# duckypad_buzz.net
KiCad netlist of a schematic drawn in EAGLE
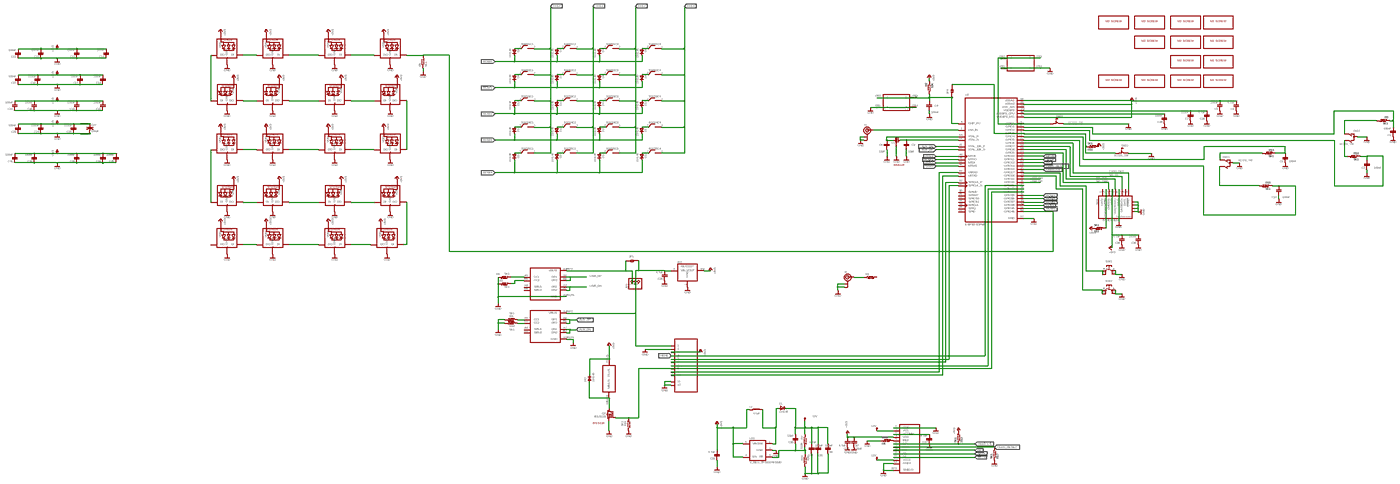
[diagram p0: schematic, sheet 1, overview]
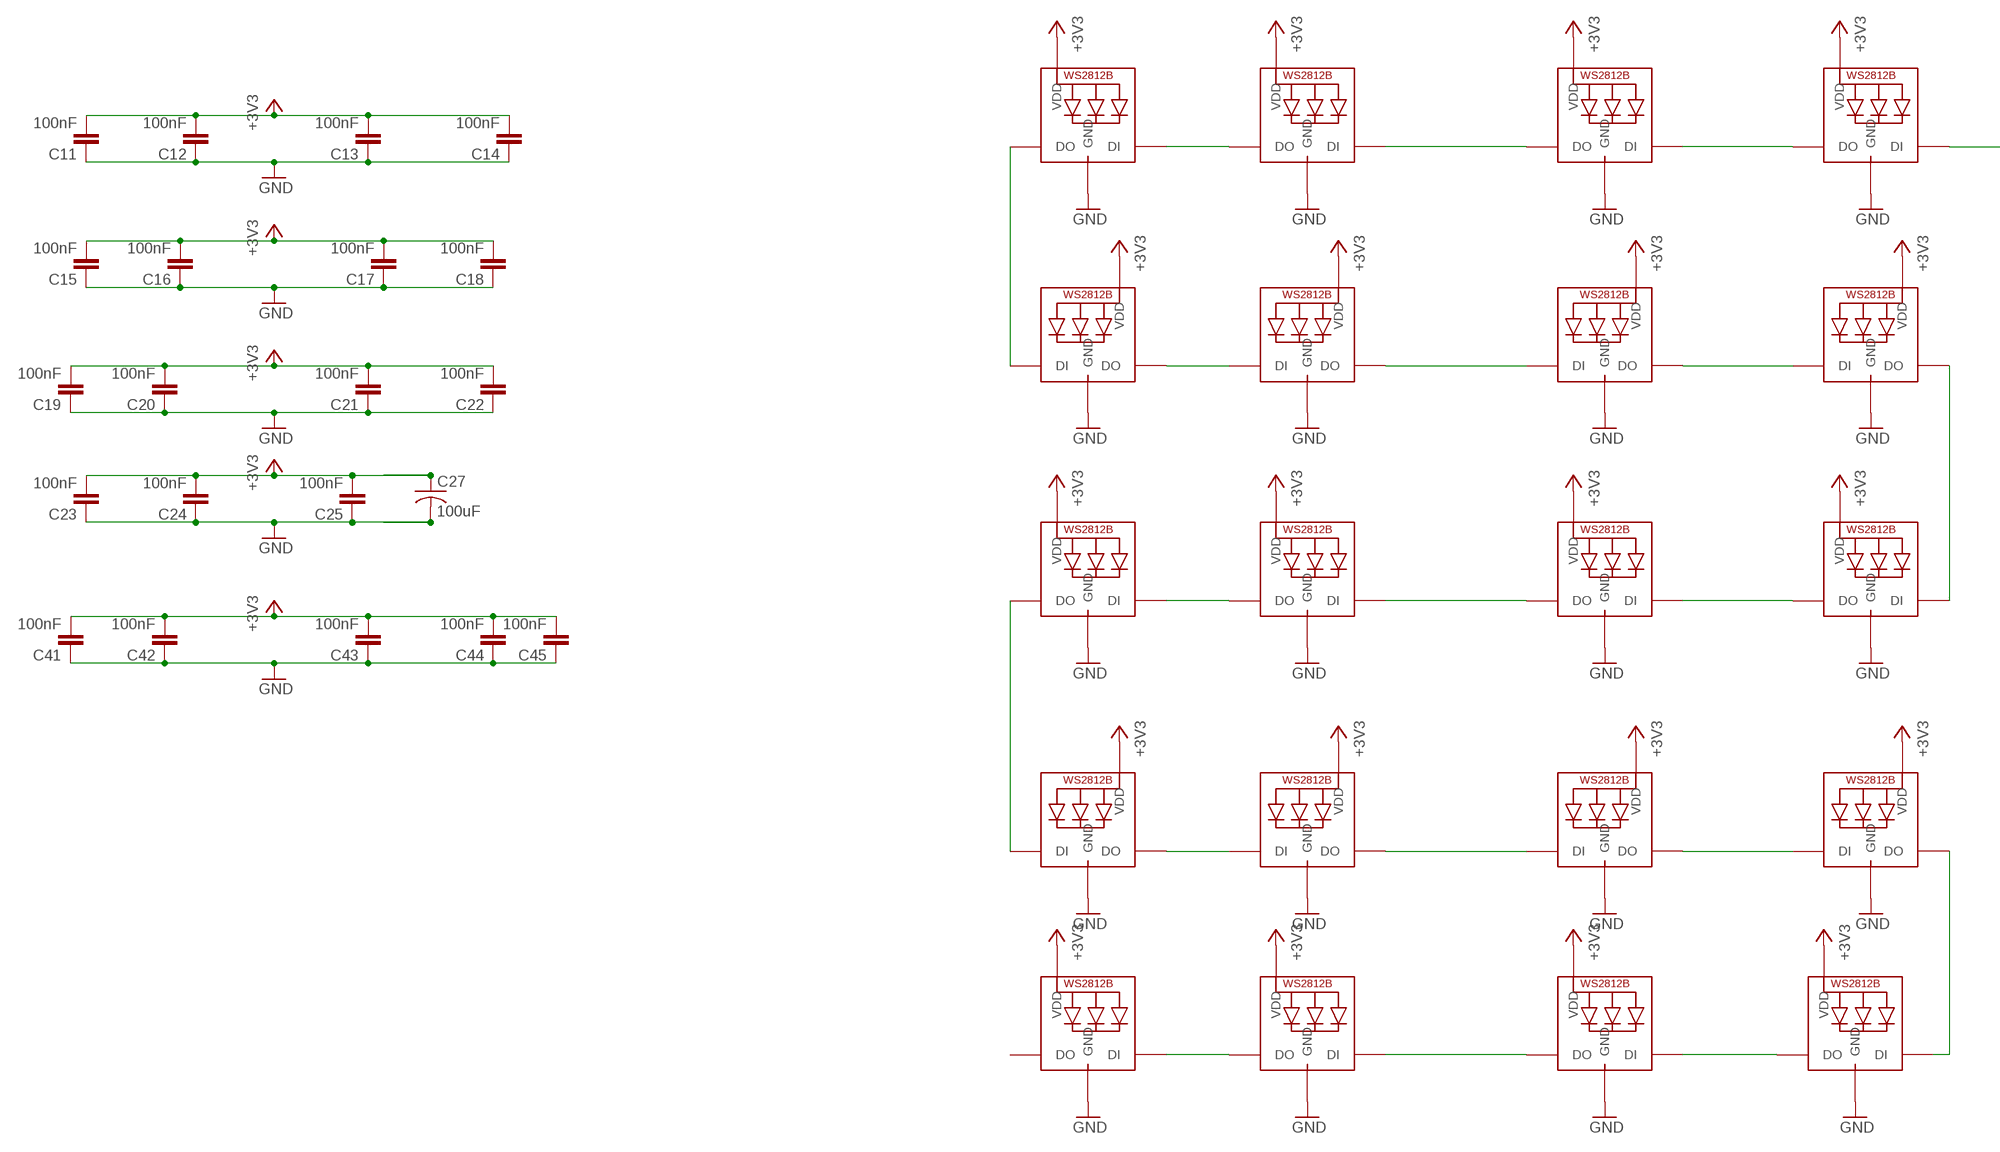
[diagram p1: schematic, sheet 1, part 1 of 4]
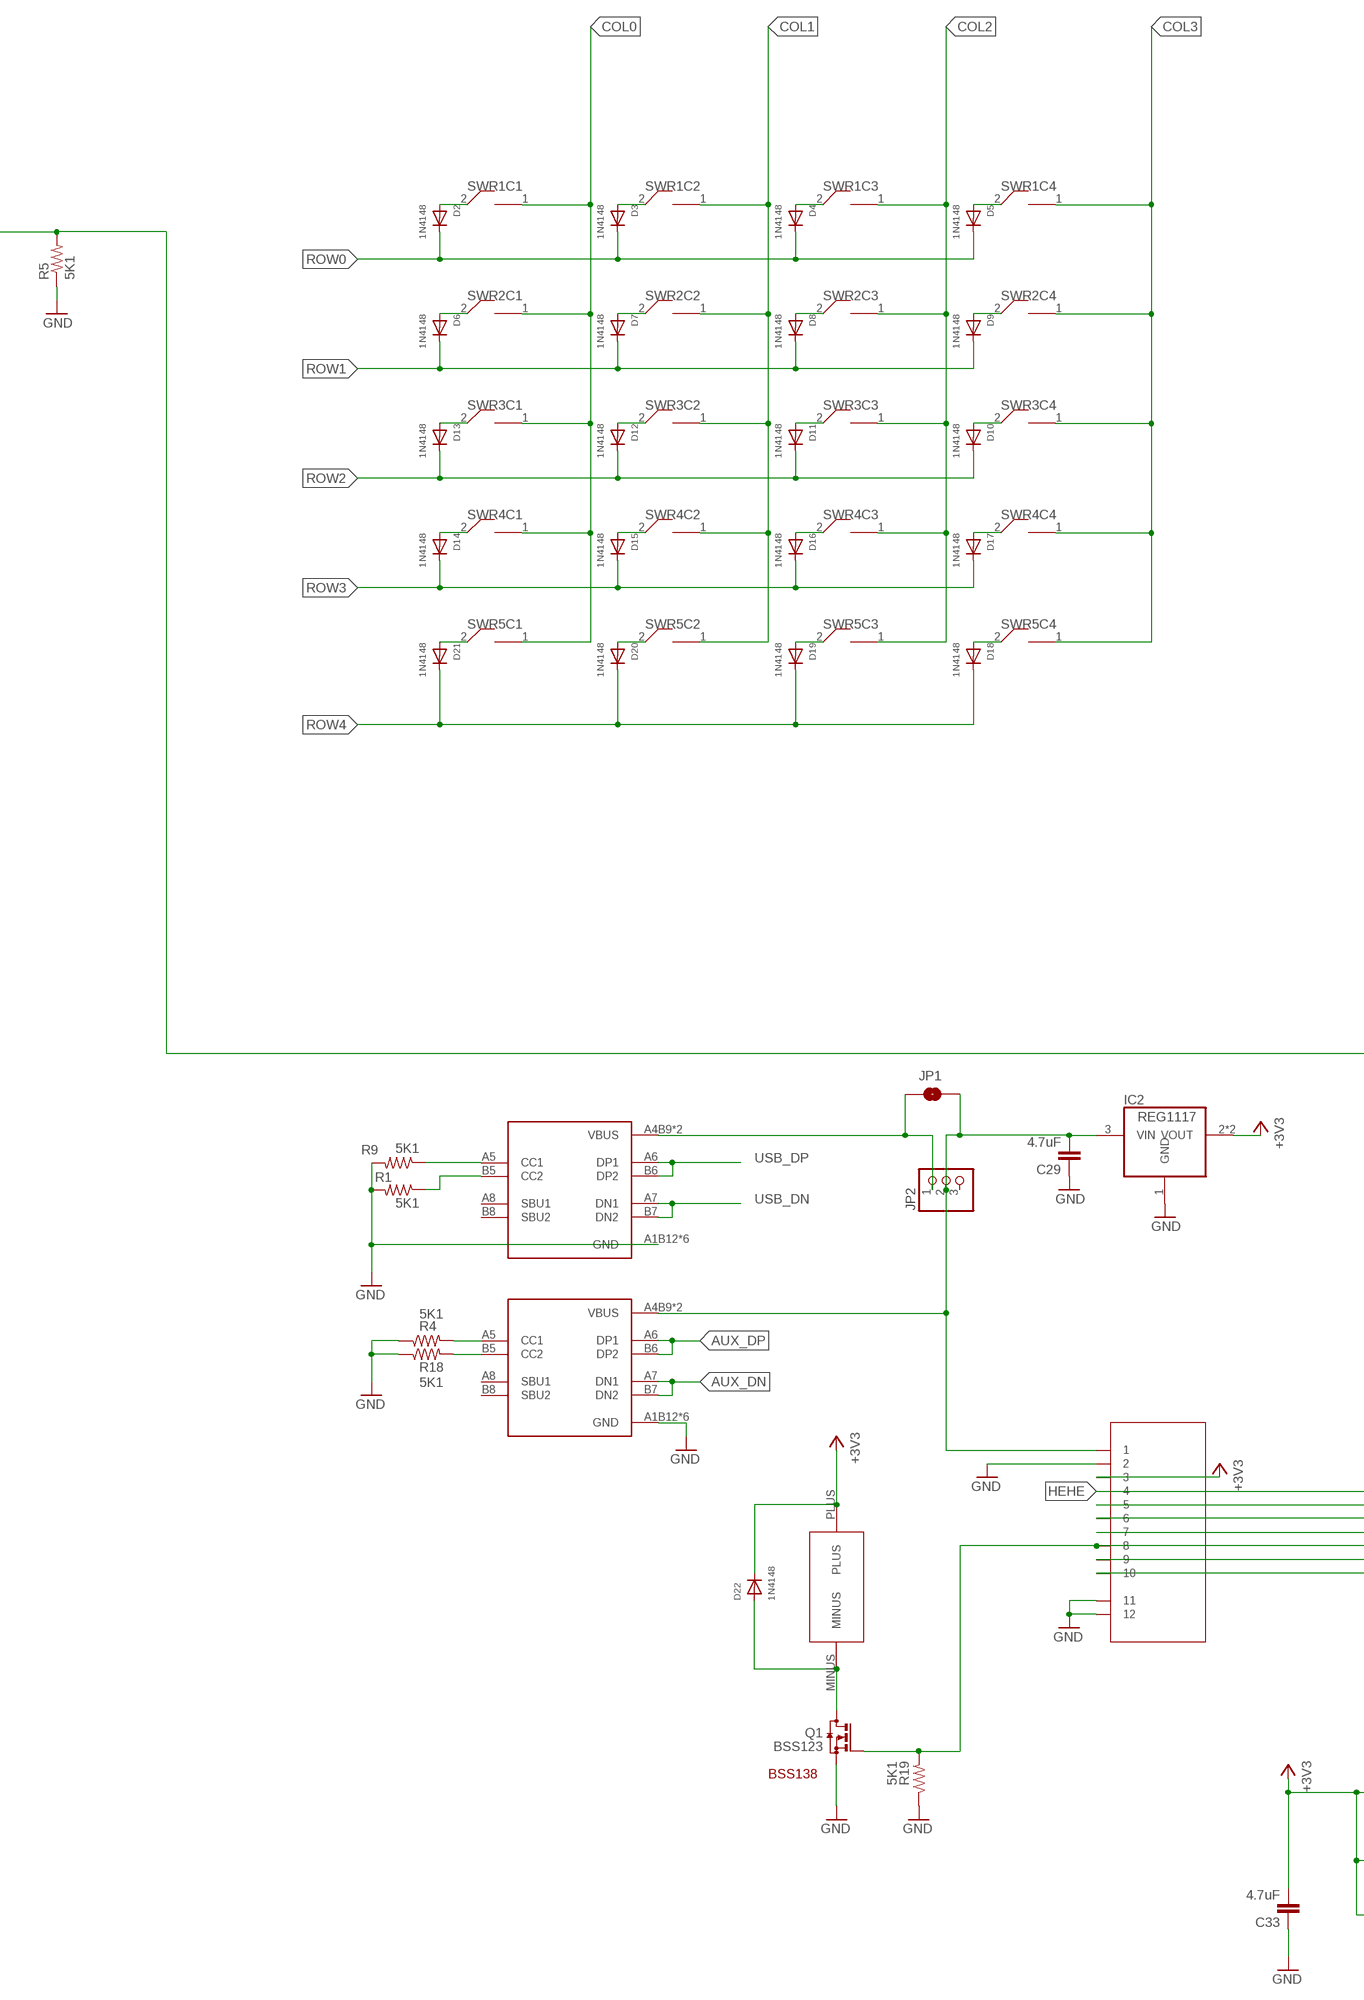
[diagram p2: schematic, sheet 1, part 2 of 4]
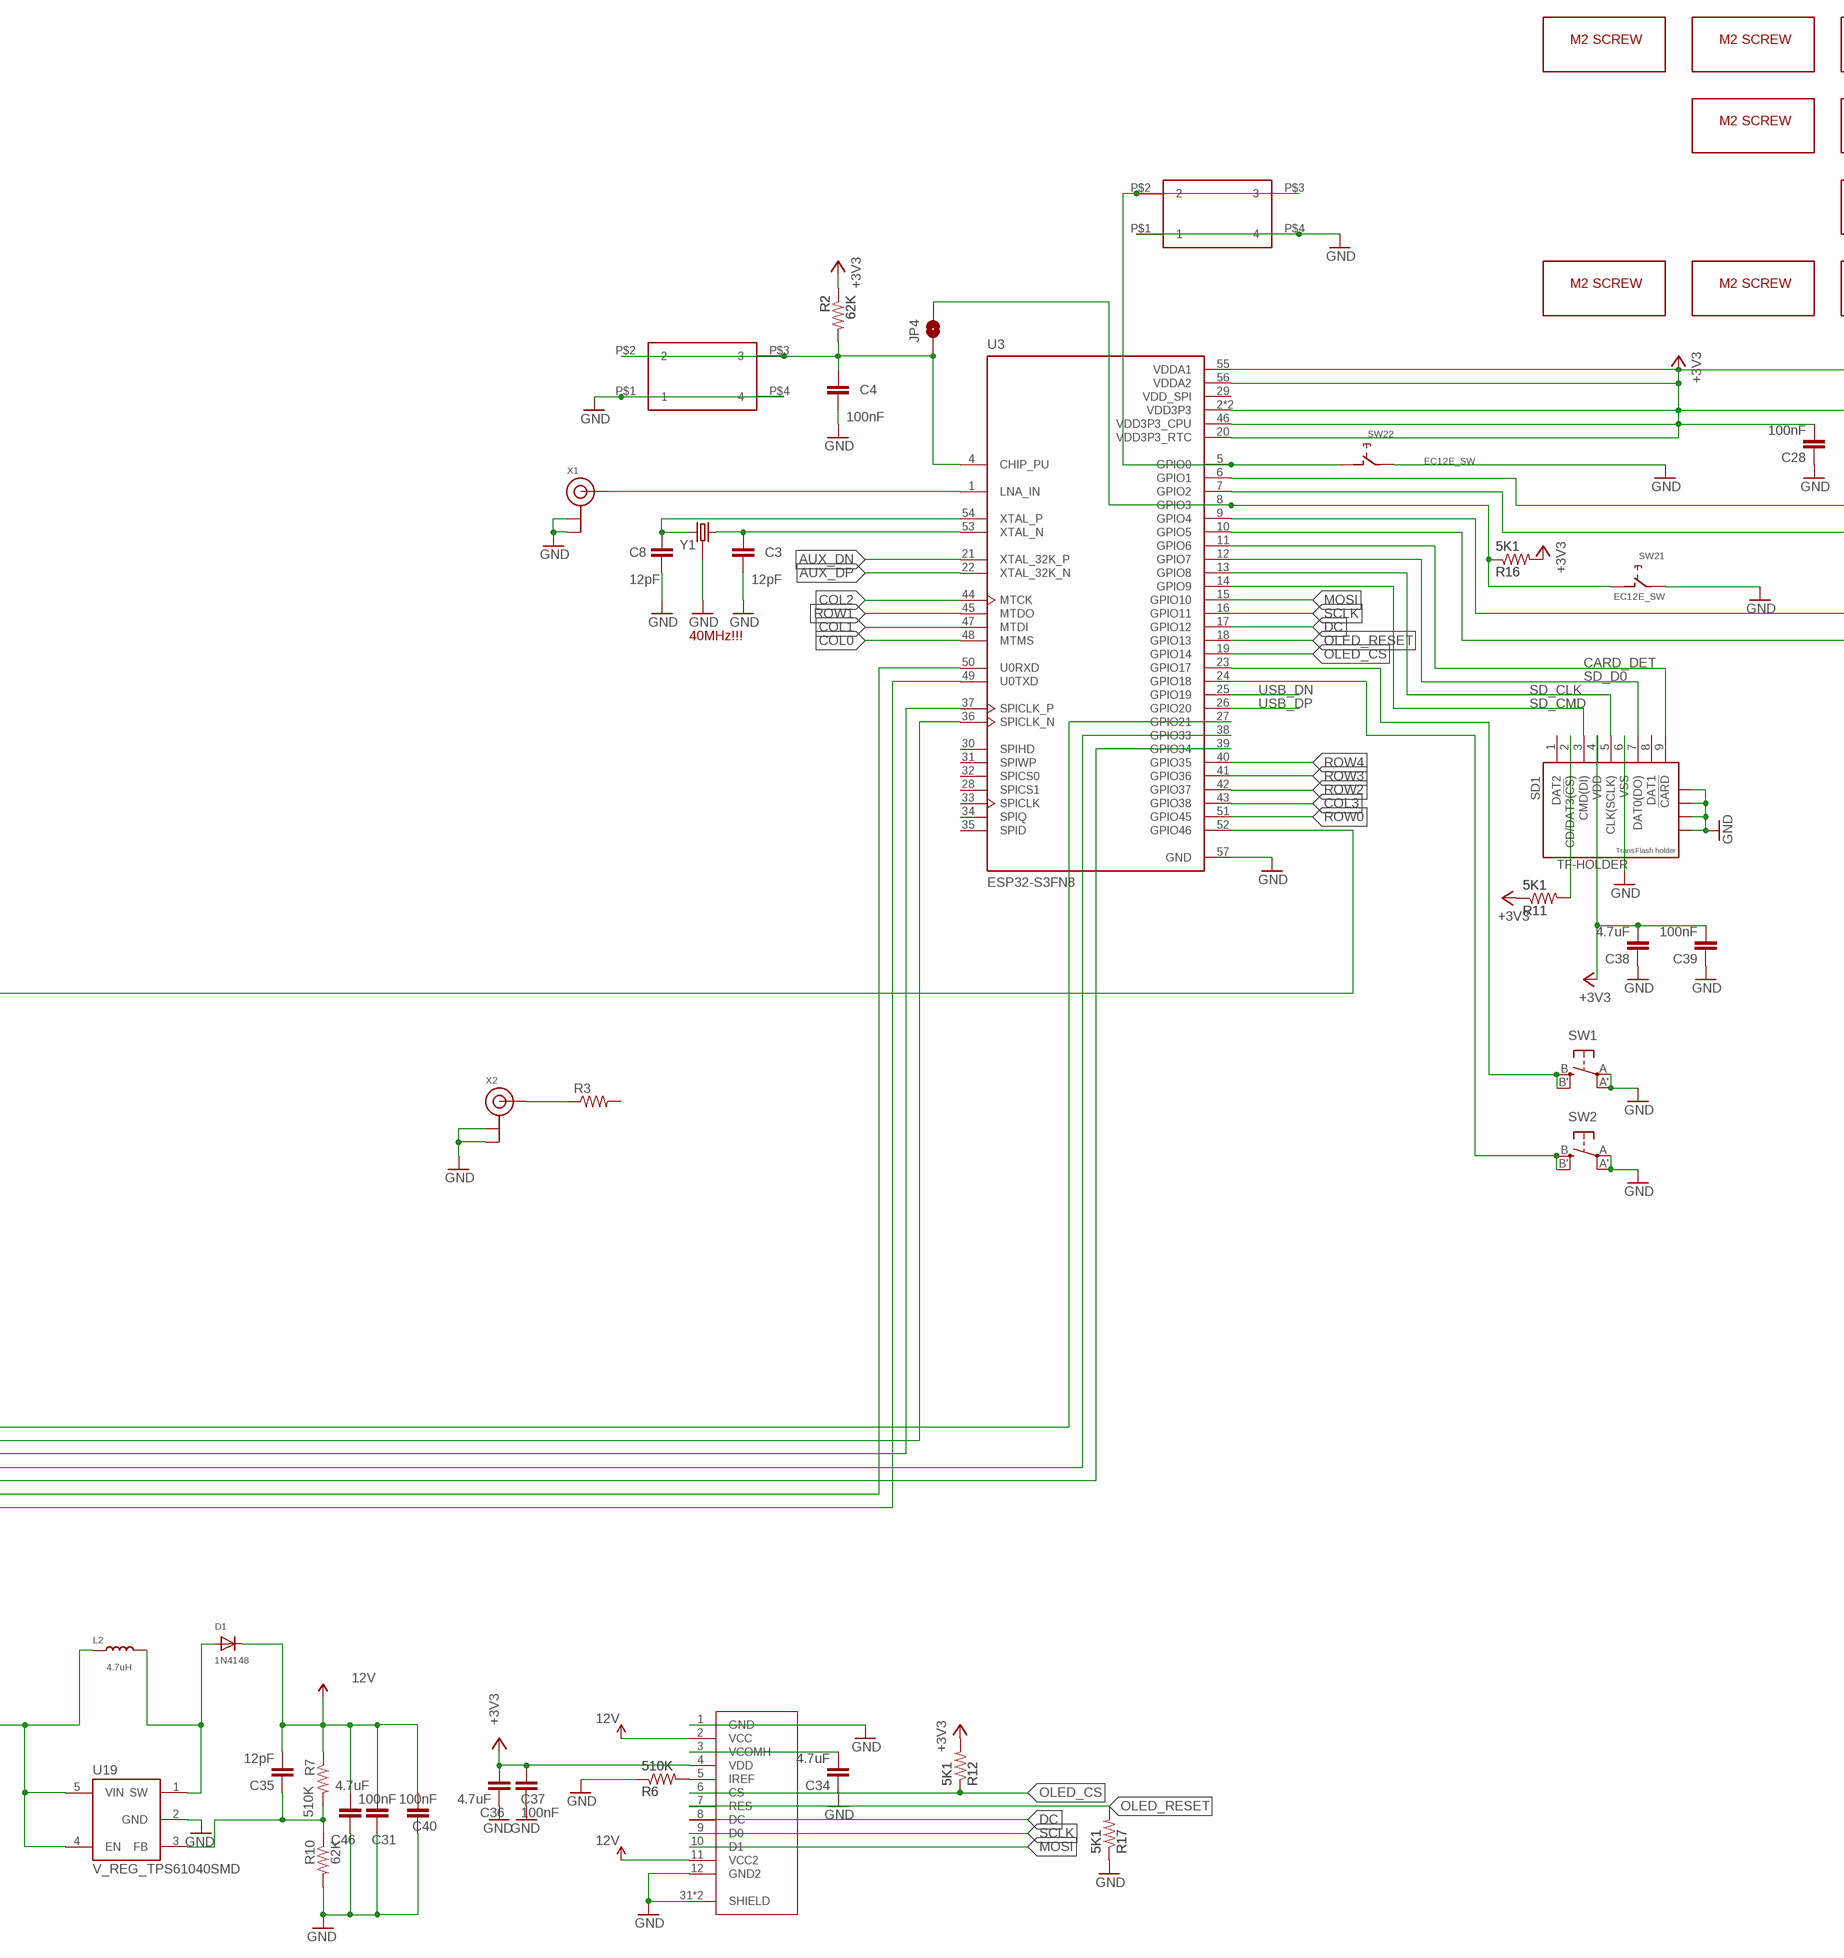
[diagram p3: schematic, sheet 1, part 3 of 4]
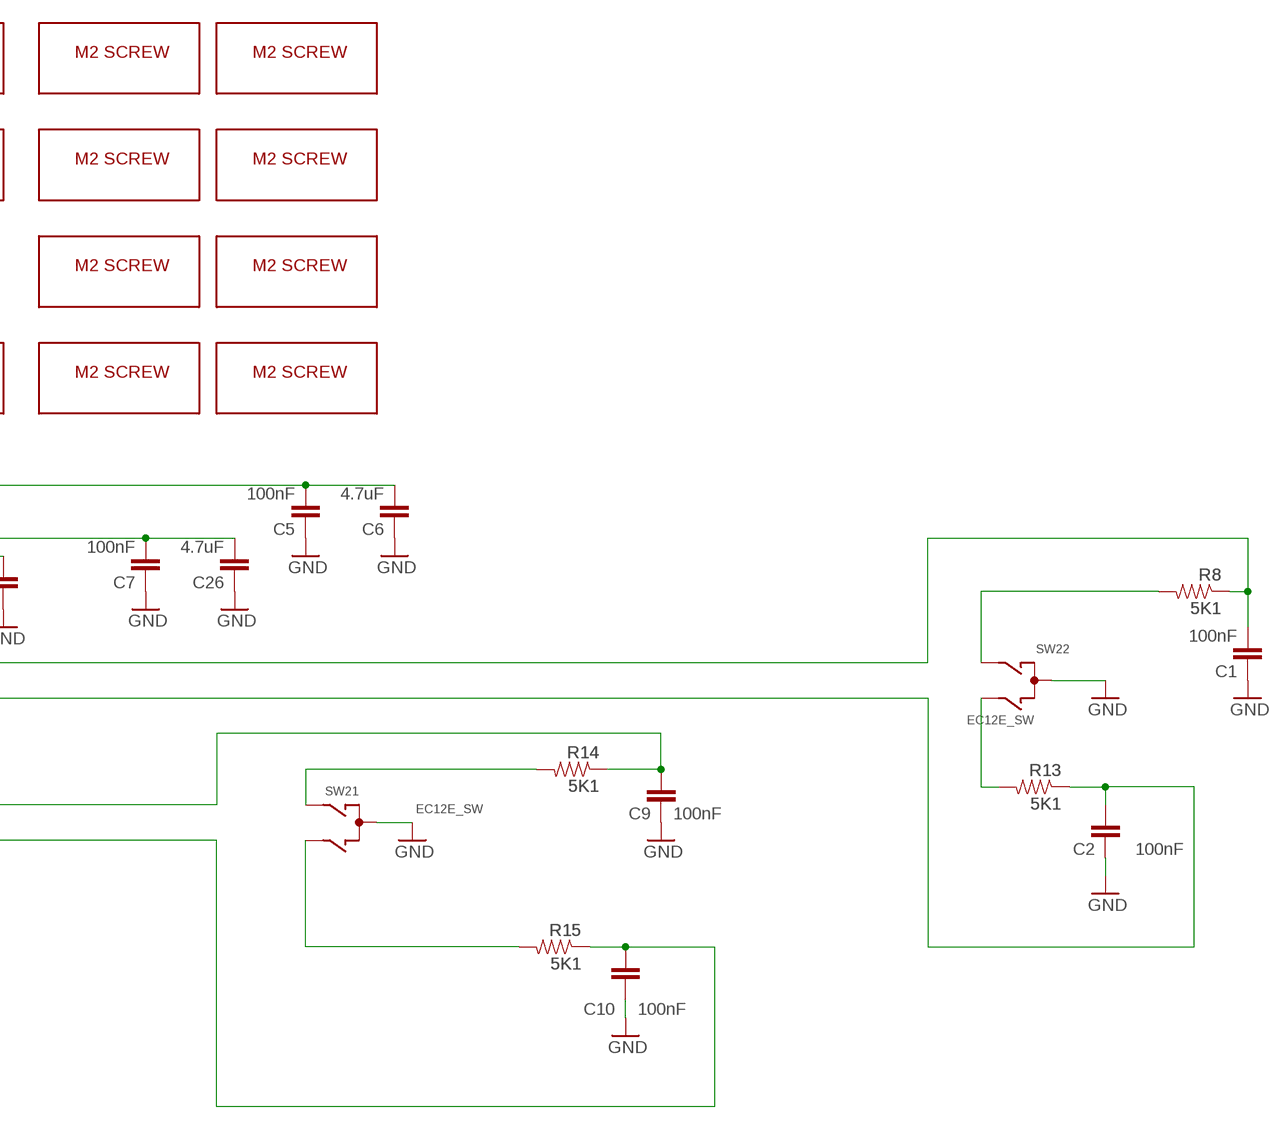
[diagram p4: schematic, sheet 1, part 4 of 4]

(export (version "E")
  (design (tool "Eeschema 10.0.6"))
  (components
    (comp (ref "BZ1")
      (value "BUZZ40402")
      (footprint "eagle-import:BUZZ")
      (libsource (lib "eagle-import") (part "BUZZ40402"))
    )
    (comp (ref "C1")
      (value "100nF")
      (footprint "eagle-import:0805")
      (libsource (lib "eagle-import") (part "CAP0805"))
    )
    (comp (ref "C2")
      (value "100nF")
      (footprint "eagle-import:0805")
      (libsource (lib "eagle-import") (part "CAP0805"))
    )
    (comp (ref "C3")
      (value "12pF")
      (footprint "eagle-import:0805")
      (libsource (lib "eagle-import") (part "CAP0805"))
    )
    (comp (ref "C4")
      (value "100nF")
      (footprint "eagle-import:0805")
      (libsource (lib "eagle-import") (part "CAP0805"))
    )
    (comp (ref "C5")
      (value "100nF")
      (footprint "eagle-import:0805")
      (libsource (lib "eagle-import") (part "CAP0805"))
    )
    (comp (ref "C6")
      (value "4.7uF")
      (footprint "eagle-import:0805")
      (libsource (lib "eagle-import") (part "CAP0805"))
    )
    (comp (ref "C7")
      (value "100nF")
      (footprint "eagle-import:0805")
      (libsource (lib "eagle-import") (part "CAP0805"))
    )
    (comp (ref "C8")
      (value "12pF")
      (footprint "eagle-import:0805")
      (libsource (lib "eagle-import") (part "CAP0805"))
    )
    (comp (ref "C9")
      (value "100nF")
      (footprint "eagle-import:0805")
      (libsource (lib "eagle-import") (part "CAP0805"))
    )
    (comp (ref "C10")
      (value "100nF")
      (footprint "eagle-import:0805")
      (libsource (lib "eagle-import") (part "CAP0805"))
    )
    (comp (ref "C11")
      (value "100nF")
      (footprint "eagle-import:0805")
      (libsource (lib "eagle-import") (part "CAP0805"))
    )
    (comp (ref "C12")
      (value "100nF")
      (footprint "eagle-import:0805")
      (libsource (lib "eagle-import") (part "CAP0805"))
    )
    (comp (ref "C13")
      (value "100nF")
      (footprint "eagle-import:0805")
      (libsource (lib "eagle-import") (part "CAP0805"))
    )
    (comp (ref "C14")
      (value "100nF")
      (footprint "eagle-import:0805")
      (libsource (lib "eagle-import") (part "CAP0805"))
    )
    (comp (ref "C15")
      (value "100nF")
      (footprint "eagle-import:0805")
      (libsource (lib "eagle-import") (part "CAP0805"))
    )
    (comp (ref "C16")
      (value "100nF")
      (footprint "eagle-import:0805")
      (libsource (lib "eagle-import") (part "CAP0805"))
    )
    (comp (ref "C17")
      (value "100nF")
      (footprint "eagle-import:0805")
      (libsource (lib "eagle-import") (part "CAP0805"))
    )
    (comp (ref "C18")
      (value "100nF")
      (footprint "eagle-import:0805")
      (libsource (lib "eagle-import") (part "CAP0805"))
    )
    (comp (ref "C19")
      (value "100nF")
      (footprint "eagle-import:0805")
      (libsource (lib "eagle-import") (part "CAP0805"))
    )
    (comp (ref "C20")
      (value "100nF")
      (footprint "eagle-import:0805")
      (libsource (lib "eagle-import") (part "CAP0805"))
    )
    (comp (ref "C21")
      (value "100nF")
      (footprint "eagle-import:0805")
      (libsource (lib "eagle-import") (part "CAP0805"))
    )
    (comp (ref "C22")
      (value "100nF")
      (footprint "eagle-import:0805")
      (libsource (lib "eagle-import") (part "CAP0805"))
    )
    (comp (ref "C23")
      (value "100nF")
      (footprint "eagle-import:0805")
      (libsource (lib "eagle-import") (part "CAP0805"))
    )
    (comp (ref "C24")
      (value "100nF")
      (footprint "eagle-import:0805")
      (libsource (lib "eagle-import") (part "CAP0805"))
    )
    (comp (ref "C25")
      (value "100nF")
      (footprint "eagle-import:0805")
      (libsource (lib "eagle-import") (part "CAP0805"))
    )
    (comp (ref "C26")
      (value "4.7uF")
      (footprint "eagle-import:0805")
      (libsource (lib "eagle-import") (part "CAP0805"))
    )
    (comp (ref "C27")
      (value "100uF")
      (footprint "eagle-import:C1210")
      (libsource (lib "eagle-import") (part "C-USC1210"))
    )
    (comp (ref "C28")
      (value "100nF")
      (footprint "eagle-import:0805")
      (libsource (lib "eagle-import") (part "CAP0805"))
    )
    (comp (ref "C29")
      (value "4.7uF")
      (footprint "eagle-import:0805")
      (libsource (lib "eagle-import") (part "CAP0805"))
    )
    (comp (ref "C31")
      (value "100nF")
      (footprint "eagle-import:0805")
      (libsource (lib "eagle-import") (part "CAP0805"))
    )
    (comp (ref "C33")
      (value "4.7uF")
      (footprint "eagle-import:0805")
      (libsource (lib "eagle-import") (part "CAP0805"))
    )
    (comp (ref "C34")
      (value "4.7uF")
      (footprint "eagle-import:0805")
      (libsource (lib "eagle-import") (part "CAP0805"))
    )
    (comp (ref "C35")
      (value "12pF")
      (footprint "eagle-import:0805")
      (libsource (lib "eagle-import") (part "CAP0805"))
    )
    (comp (ref "C36")
      (value "4.7uF")
      (footprint "eagle-import:0805")
      (libsource (lib "eagle-import") (part "CAP0805"))
    )
    (comp (ref "C37")
      (value "100nF")
      (footprint "eagle-import:0805")
      (libsource (lib "eagle-import") (part "CAP0805"))
    )
    (comp (ref "C38")
      (value "4.7uF")
      (footprint "eagle-import:0805")
      (libsource (lib "eagle-import") (part "CAP0805"))
    )
    (comp (ref "C39")
      (value "100nF")
      (footprint "eagle-import:0805")
      (libsource (lib "eagle-import") (part "CAP0805"))
    )
    (comp (ref "C40")
      (value "100nF")
      (footprint "eagle-import:0805")
      (libsource (lib "eagle-import") (part "CAP0805"))
    )
    (comp (ref "C41")
      (value "100nF")
      (footprint "eagle-import:0805")
      (libsource (lib "eagle-import") (part "CAP0805"))
    )
    (comp (ref "C42")
      (value "100nF")
      (footprint "eagle-import:0805")
      (libsource (lib "eagle-import") (part "CAP0805"))
    )
    (comp (ref "C43")
      (value "100nF")
      (footprint "eagle-import:0805")
      (libsource (lib "eagle-import") (part "CAP0805"))
    )
    (comp (ref "C44")
      (value "100nF")
      (footprint "eagle-import:0805")
      (libsource (lib "eagle-import") (part "CAP0805"))
    )
    (comp (ref "C45")
      (value "100nF")
      (footprint "eagle-import:0805")
      (libsource (lib "eagle-import") (part "CAP0805"))
    )
    (comp (ref "C46")
      (value "4.7uF")
      (footprint "eagle-import:0805")
      (libsource (lib "eagle-import") (part "CAP0805"))
    )
    (comp (ref "D1")
      (value "1N4148")
      (footprint "eagle-import:ADAFRUIT_CHANGED_SOD-123")
      (libsource (lib "eagle-import") (part "ADAFRUIT_CHANGED_DIODESOD-123"))
    )
    (comp (ref "D2")
      (value "1N4148")
      (footprint "eagle-import:ADAFRUIT_CHANGED_SOD-123")
      (libsource (lib "eagle-import") (part "ADAFRUIT_CHANGED_DIODESOD-123"))
    )
    (comp (ref "D3")
      (value "1N4148")
      (footprint "eagle-import:ADAFRUIT_CHANGED_SOD-123")
      (libsource (lib "eagle-import") (part "ADAFRUIT_CHANGED_DIODESOD-123"))
    )
    (comp (ref "D4")
      (value "1N4148")
      (footprint "eagle-import:ADAFRUIT_CHANGED_SOD-123")
      (libsource (lib "eagle-import") (part "ADAFRUIT_CHANGED_DIODESOD-123"))
    )
    (comp (ref "D5")
      (value "1N4148")
      (footprint "eagle-import:ADAFRUIT_CHANGED_SOD-123")
      (libsource (lib "eagle-import") (part "ADAFRUIT_CHANGED_DIODESOD-123"))
    )
    (comp (ref "D6")
      (value "1N4148")
      (footprint "eagle-import:ADAFRUIT_CHANGED_SOD-123")
      (libsource (lib "eagle-import") (part "ADAFRUIT_CHANGED_DIODESOD-123"))
    )
    (comp (ref "D7")
      (value "1N4148")
      (footprint "eagle-import:ADAFRUIT_CHANGED_SOD-123")
      (libsource (lib "eagle-import") (part "ADAFRUIT_CHANGED_DIODESOD-123"))
    )
    (comp (ref "D8")
      (value "1N4148")
      (footprint "eagle-import:ADAFRUIT_CHANGED_SOD-123")
      (libsource (lib "eagle-import") (part "ADAFRUIT_CHANGED_DIODESOD-123"))
    )
    (comp (ref "D9")
      (value "1N4148")
      (footprint "eagle-import:ADAFRUIT_CHANGED_SOD-123")
      (libsource (lib "eagle-import") (part "ADAFRUIT_CHANGED_DIODESOD-123"))
    )
    (comp (ref "D10")
      (value "1N4148")
      (footprint "eagle-import:ADAFRUIT_CHANGED_SOD-123")
      (libsource (lib "eagle-import") (part "ADAFRUIT_CHANGED_DIODESOD-123"))
    )
    (comp (ref "D11")
      (value "1N4148")
      (footprint "eagle-import:ADAFRUIT_CHANGED_SOD-123")
      (libsource (lib "eagle-import") (part "ADAFRUIT_CHANGED_DIODESOD-123"))
    )
    (comp (ref "D12")
      (value "1N4148")
      (footprint "eagle-import:ADAFRUIT_CHANGED_SOD-123")
      (libsource (lib "eagle-import") (part "ADAFRUIT_CHANGED_DIODESOD-123"))
    )
    (comp (ref "D13")
      (value "1N4148")
      (footprint "eagle-import:ADAFRUIT_CHANGED_SOD-123")
      (libsource (lib "eagle-import") (part "ADAFRUIT_CHANGED_DIODESOD-123"))
    )
    (comp (ref "D14")
      (value "1N4148")
      (footprint "eagle-import:ADAFRUIT_CHANGED_SOD-123")
      (libsource (lib "eagle-import") (part "ADAFRUIT_CHANGED_DIODESOD-123"))
    )
    (comp (ref "D15")
      (value "1N4148")
      (footprint "eagle-import:ADAFRUIT_CHANGED_SOD-123")
      (libsource (lib "eagle-import") (part "ADAFRUIT_CHANGED_DIODESOD-123"))
    )
    (comp (ref "D16")
      (value "1N4148")
      (footprint "eagle-import:ADAFRUIT_CHANGED_SOD-123")
      (libsource (lib "eagle-import") (part "ADAFRUIT_CHANGED_DIODESOD-123"))
    )
    (comp (ref "D17")
      (value "1N4148")
      (footprint "eagle-import:ADAFRUIT_CHANGED_SOD-123")
      (libsource (lib "eagle-import") (part "ADAFRUIT_CHANGED_DIODESOD-123"))
    )
    (comp (ref "D18")
      (value "1N4148")
      (footprint "eagle-import:ADAFRUIT_CHANGED_SOD-123")
      (libsource (lib "eagle-import") (part "ADAFRUIT_CHANGED_DIODESOD-123"))
    )
    (comp (ref "D19")
      (value "1N4148")
      (footprint "eagle-import:ADAFRUIT_CHANGED_SOD-123")
      (libsource (lib "eagle-import") (part "ADAFRUIT_CHANGED_DIODESOD-123"))
    )
    (comp (ref "D20")
      (value "1N4148")
      (footprint "eagle-import:ADAFRUIT_CHANGED_SOD-123")
      (libsource (lib "eagle-import") (part "ADAFRUIT_CHANGED_DIODESOD-123"))
    )
    (comp (ref "D21")
      (value "1N4148")
      (footprint "eagle-import:ADAFRUIT_CHANGED_SOD-123")
      (libsource (lib "eagle-import") (part "ADAFRUIT_CHANGED_DIODESOD-123"))
    )
    (comp (ref "D22")
      (value "1N4148")
      (footprint "eagle-import:ADAFRUIT_CHANGED_SOD-123")
      (libsource (lib "eagle-import") (part "ADAFRUIT_CHANGED_DIODESOD-123"))
    )
    (comp (ref "IC2")
      (value "REG1117")
      (footprint "eagle-import:SOT223")
      (libsource (lib "eagle-import") (part "REG1117"))
    )
    (comp (ref "JP1")
      (value "JUMPER-SMT_2_NO_NO-SILK")
      (footprint "eagle-import:SMT-JUMPER_2_NO_NO-SILK")
      (libsource (lib "eagle-import") (part "JUMPER-SMT_2_NO_NO-SILK"))
    )
    (comp (ref "JP2")
      (value "PINHD-1X3CB")
      (footprint "eagle-import:1X03-CLEANBIG")
      (libsource (lib "eagle-import") (part "PINHD-1X3CB"))
    )
    (comp (ref "JP4")
      (value "JUMPER-SMT_2_NO_NO-SILK")
      (footprint "eagle-import:SMT-JUMPER_2_NO_NO-SILK")
      (libsource (lib "eagle-import") (part "JUMPER-SMT_2_NO_NO-SILK"))
    )
    (comp (ref "L2")
      (value "4.7uH")
      (footprint "eagle-import:L4030")
      (libsource (lib "eagle-import") (part "L-4030"))
    )
    (comp (ref "LED_R1C1")
      (value "WS2812B")
      (footprint "eagle-import:REVERSE_MNT")
      (libsource (lib "eagle-import") (part "WS2812B"))
    )
    (comp (ref "LED_R1C2")
      (value "WS2812B")
      (footprint "eagle-import:REVERSE_MNT")
      (libsource (lib "eagle-import") (part "WS2812B"))
    )
    (comp (ref "LED_R1C3")
      (value "WS2812B")
      (footprint "eagle-import:REVERSE_MNT")
      (libsource (lib "eagle-import") (part "WS2812B"))
    )
    (comp (ref "LED_R1C4")
      (value "WS2812B")
      (footprint "eagle-import:REVERSE_MNT")
      (libsource (lib "eagle-import") (part "WS2812B"))
    )
    (comp (ref "LED_R2C1")
      (value "WS2812B")
      (footprint "eagle-import:REVERSE_MNT")
      (libsource (lib "eagle-import") (part "WS2812B"))
    )
    (comp (ref "LED_R2C2")
      (value "WS2812B")
      (footprint "eagle-import:REVERSE_MNT")
      (libsource (lib "eagle-import") (part "WS2812B"))
    )
    (comp (ref "LED_R2C3")
      (value "WS2812B")
      (footprint "eagle-import:REVERSE_MNT")
      (libsource (lib "eagle-import") (part "WS2812B"))
    )
    (comp (ref "LED_R2C4")
      (value "WS2812B")
      (footprint "eagle-import:REVERSE_MNT")
      (libsource (lib "eagle-import") (part "WS2812B"))
    )
    (comp (ref "LED_R3C1")
      (value "WS2812B")
      (footprint "eagle-import:REVERSE_MNT")
      (libsource (lib "eagle-import") (part "WS2812B"))
    )
    (comp (ref "LED_R3C2")
      (value "WS2812B")
      (footprint "eagle-import:REVERSE_MNT")
      (libsource (lib "eagle-import") (part "WS2812B"))
    )
    (comp (ref "LED_R3C3")
      (value "WS2812B")
      (footprint "eagle-import:REVERSE_MNT")
      (libsource (lib "eagle-import") (part "WS2812B"))
    )
    (comp (ref "LED_R3C4")
      (value "WS2812B")
      (footprint "eagle-import:REVERSE_MNT")
      (libsource (lib "eagle-import") (part "WS2812B"))
    )
    (comp (ref "LED_R4C1")
      (value "WS2812B")
      (footprint "eagle-import:REVERSE_MNT")
      (libsource (lib "eagle-import") (part "WS2812B"))
    )
    (comp (ref "LED_R4C2")
      (value "WS2812B")
      (footprint "eagle-import:REVERSE_MNT")
      (libsource (lib "eagle-import") (part "WS2812B"))
    )
    (comp (ref "LED_R4C3")
      (value "WS2812B")
      (footprint "eagle-import:REVERSE_MNT")
      (libsource (lib "eagle-import") (part "WS2812B"))
    )
    (comp (ref "LED_R4C4")
      (value "WS2812B")
      (footprint "eagle-import:REVERSE_MNT")
      (libsource (lib "eagle-import") (part "WS2812B"))
    )
    (comp (ref "LED_R5C1")
      (value "WS2812B")
      (footprint "eagle-import:REVERSE_MNT")
      (libsource (lib "eagle-import") (part "WS2812B"))
    )
    (comp (ref "LED_R5C2")
      (value "WS2812B")
      (footprint "eagle-import:REVERSE_MNT")
      (libsource (lib "eagle-import") (part "WS2812B"))
    )
    (comp (ref "LED_R5C3")
      (value "WS2812B")
      (footprint "eagle-import:REVERSE_MNT")
      (libsource (lib "eagle-import") (part "WS2812B"))
    )
    (comp (ref "LED_R5C4")
      (value "WS2812B")
      (footprint "eagle-import:REVERSE_MNT")
      (libsource (lib "eagle-import") (part "WS2812B"))
    )
    (comp (ref "Q1")
      (value "BSS123")
      (footprint "eagle-import:SOT23")
      (libsource (lib "eagle-import") (part "BSS123"))
    )
    (comp (ref "R1")
      (value "5K1")
      (footprint "eagle-import:0805")
      (libsource (lib "eagle-import") (part "joyAnalog_RESISTOR0805-RES"))
    )
    (comp (ref "R2")
      (value "62K")
      (footprint "eagle-import:0805")
      (libsource (lib "eagle-import") (part "joyAnalog_RESISTOR0805-RES"))
    )
    (comp (ref "R3")
      (value "R-US_R2010")
      (footprint "eagle-import:R2010")
      (libsource (lib "eagle-import") (part "R-US_R2010"))
    )
    (comp (ref "R4")
      (value "5K1")
      (footprint "eagle-import:0805")
      (libsource (lib "eagle-import") (part "joyAnalog_RESISTOR0805-RES"))
    )
    (comp (ref "R5")
      (value "5K1")
      (footprint "eagle-import:0805")
      (libsource (lib "eagle-import") (part "RESISTOR0805-RES"))
    )
    (comp (ref "R6")
      (value "510K")
      (footprint "eagle-import:0805")
      (libsource (lib "eagle-import") (part "joyAnalog_RESISTOR0805-RES"))
    )
    (comp (ref "R7")
      (value "510K")
      (footprint "eagle-import:0805")
      (libsource (lib "eagle-import") (part "joyAnalog_RESISTOR0805-RES"))
    )
    (comp (ref "R8")
      (value "5K1")
      (footprint "eagle-import:0805")
      (libsource (lib "eagle-import") (part "joyAnalog_RESISTOR0805-RES"))
    )
    (comp (ref "R9")
      (value "5K1")
      (footprint "eagle-import:0805")
      (libsource (lib "eagle-import") (part "joyAnalog_RESISTOR0805-RES"))
    )
    (comp (ref "R10")
      (value "62K")
      (footprint "eagle-import:0805")
      (libsource (lib "eagle-import") (part "joyAnalog_RESISTOR0805-RES"))
    )
    (comp (ref "R11")
      (value "5K1")
      (footprint "eagle-import:0805")
      (libsource (lib "eagle-import") (part "joyAnalog_RESISTOR0805-RES"))
    )
    (comp (ref "R12")
      (value "5K1")
      (footprint "eagle-import:0805")
      (libsource (lib "eagle-import") (part "joyAnalog_RESISTOR0805-RES"))
    )
    (comp (ref "R13")
      (value "5K1")
      (footprint "eagle-import:0805")
      (libsource (lib "eagle-import") (part "joyAnalog_RESISTOR0805-RES"))
    )
    (comp (ref "R14")
      (value "5K1")
      (footprint "eagle-import:0805")
      (libsource (lib "eagle-import") (part "joyAnalog_RESISTOR0805-RES"))
    )
    (comp (ref "R15")
      (value "5K1")
      (footprint "eagle-import:0805")
      (libsource (lib "eagle-import") (part "joyAnalog_RESISTOR0805-RES"))
    )
    (comp (ref "R16")
      (value "5K1")
      (footprint "eagle-import:0805")
      (libsource (lib "eagle-import") (part "joyAnalog_RESISTOR0805-RES"))
    )
    (comp (ref "R17")
      (value "5K1")
      (footprint "eagle-import:0805")
      (libsource (lib "eagle-import") (part "joyAnalog_RESISTOR0805-RES"))
    )
    (comp (ref "R18")
      (value "5K1")
      (footprint "eagle-import:0805")
      (libsource (lib "eagle-import") (part "joyAnalog_RESISTOR0805-RES"))
    )
    (comp (ref "R19")
      (value "5K1")
      (footprint "eagle-import:0805")
      (libsource (lib "eagle-import") (part "joyAnalog_RESISTOR0805-RES"))
    )
    (comp (ref "SD1")
      (value "TF-HOLDER")
      (footprint "eagle-import:TF-PULL")
      (libsource (lib "eagle-import") (part "TF-HOLDER"))
    )
    (comp (ref "SH1")
      (value "SH10P")
      (footprint "eagle-import:DUCKYPAD_SM12B-SSR-H-TB")
      (libsource (lib "eagle-import") (part "SH10P"))
    )
    (comp (ref "SW1")
      (value "SPST_TACT-EVQQ2")
      (footprint "eagle-import:EVQ-Q2")
      (libsource (lib "eagle-import") (part "SPST_TACT-EVQQ2"))
    )
    (comp (ref "SW2")
      (value "SPST_TACT-EVQQ2")
      (footprint "eagle-import:EVQ-Q2")
      (libsource (lib "eagle-import") (part "SPST_TACT-EVQQ2"))
    )
    (comp (ref "SW3")
      (value "324_SW324_SWITCH_FOOT_HOLE")
      (footprint "eagle-import:342_SWICH_FOOT_HOLE")
      (libsource (lib "eagle-import") (part "324_SW324_SWITCH_FOOT_HOLE"))
    )
    (comp (ref "SW4")
      (value "324_SW324_SWITCH_FOOT_HOLE")
      (footprint "eagle-import:342_SWICH_FOOT_HOLE")
      (libsource (lib "eagle-import") (part "324_SW324_SWITCH_FOOT_HOLE"))
    )
    (comp (ref "SW21")
      (value "EC12E_SW")
      (footprint "eagle-import:ALPS_EC12E_SW")
      (fields (field (name "MPN") "EC12E2424407"))
      (libsource (lib "eagle-import") (part "EC12E_SW"))
    )
    (comp (ref "SW22")
      (value "EC12E_SW")
      (footprint "eagle-import:ALPS_EC12E_SW")
      (fields (field (name "MPN") "EC12E2424407"))
      (libsource (lib "eagle-import") (part "EC12E_SW"))
    )
    (comp (ref "SWR1C1")
      (value "KAILH_SWITCH_SOCKET_KAILH_SWITCH_SOCKET")
      (footprint "eagle-import:KAILH_SWITCH_SOCKET_SWITCH_SOCKET")
      (libsource (lib "eagle-import") (part "KAILH_SWITCH_SOCKET_KAILH_SWITCH_SOCKET"))
    )
    (comp (ref "SWR1C2")
      (value "KAILH_SWITCH_SOCKET_KAILH_SWITCH_SOCKET")
      (footprint "eagle-import:KAILH_SWITCH_SOCKET_SWITCH_SOCKET")
      (libsource (lib "eagle-import") (part "KAILH_SWITCH_SOCKET_KAILH_SWITCH_SOCKET"))
    )
    (comp (ref "SWR1C3")
      (value "KAILH_SWITCH_SOCKET_KAILH_SWITCH_SOCKET")
      (footprint "eagle-import:KAILH_SWITCH_SOCKET_SWITCH_SOCKET")
      (libsource (lib "eagle-import") (part "KAILH_SWITCH_SOCKET_KAILH_SWITCH_SOCKET"))
    )
    (comp (ref "SWR1C4")
      (value "KAILH_SWITCH_SOCKET_KAILH_SWITCH_SOCKET")
      (footprint "eagle-import:KAILH_SWITCH_SOCKET_SWITCH_SOCKET")
      (libsource (lib "eagle-import") (part "KAILH_SWITCH_SOCKET_KAILH_SWITCH_SOCKET"))
    )
    (comp (ref "SWR2C1")
      (value "KAILH_SWITCH_SOCKET_KAILH_SWITCH_SOCKET")
      (footprint "eagle-import:KAILH_SWITCH_SOCKET_SWITCH_SOCKET")
      (libsource (lib "eagle-import") (part "KAILH_SWITCH_SOCKET_KAILH_SWITCH_SOCKET"))
    )
    (comp (ref "SWR2C2")
      (value "KAILH_SWITCH_SOCKET_KAILH_SWITCH_SOCKET")
      (footprint "eagle-import:KAILH_SWITCH_SOCKET_SWITCH_SOCKET")
      (libsource (lib "eagle-import") (part "KAILH_SWITCH_SOCKET_KAILH_SWITCH_SOCKET"))
    )
    (comp (ref "SWR2C3")
      (value "KAILH_SWITCH_SOCKET_KAILH_SWITCH_SOCKET")
      (footprint "eagle-import:KAILH_SWITCH_SOCKET_SWITCH_SOCKET")
      (libsource (lib "eagle-import") (part "KAILH_SWITCH_SOCKET_KAILH_SWITCH_SOCKET"))
    )
    (comp (ref "SWR2C4")
      (value "KAILH_SWITCH_SOCKET_KAILH_SWITCH_SOCKET")
      (footprint "eagle-import:KAILH_SWITCH_SOCKET_SWITCH_SOCKET")
      (libsource (lib "eagle-import") (part "KAILH_SWITCH_SOCKET_KAILH_SWITCH_SOCKET"))
    )
    (comp (ref "SWR3C1")
      (value "KAILH_SWITCH_SOCKET_KAILH_SWITCH_SOCKET")
      (footprint "eagle-import:KAILH_SWITCH_SOCKET_SWITCH_SOCKET")
      (libsource (lib "eagle-import") (part "KAILH_SWITCH_SOCKET_KAILH_SWITCH_SOCKET"))
    )
    (comp (ref "SWR3C2")
      (value "KAILH_SWITCH_SOCKET_KAILH_SWITCH_SOCKET")
      (footprint "eagle-import:KAILH_SWITCH_SOCKET_SWITCH_SOCKET")
      (libsource (lib "eagle-import") (part "KAILH_SWITCH_SOCKET_KAILH_SWITCH_SOCKET"))
    )
    (comp (ref "SWR3C3")
      (value "KAILH_SWITCH_SOCKET_KAILH_SWITCH_SOCKET")
      (footprint "eagle-import:KAILH_SWITCH_SOCKET_SWITCH_SOCKET")
      (libsource (lib "eagle-import") (part "KAILH_SWITCH_SOCKET_KAILH_SWITCH_SOCKET"))
    )
    (comp (ref "SWR3C4")
      (value "KAILH_SWITCH_SOCKET_KAILH_SWITCH_SOCKET")
      (footprint "eagle-import:KAILH_SWITCH_SOCKET_SWITCH_SOCKET")
      (libsource (lib "eagle-import") (part "KAILH_SWITCH_SOCKET_KAILH_SWITCH_SOCKET"))
    )
    (comp (ref "SWR4C1")
      (value "KAILH_SWITCH_SOCKET_KAILH_SWITCH_SOCKET")
      (footprint "eagle-import:KAILH_SWITCH_SOCKET_SWITCH_SOCKET")
      (libsource (lib "eagle-import") (part "KAILH_SWITCH_SOCKET_KAILH_SWITCH_SOCKET"))
    )
    (comp (ref "SWR4C2")
      (value "KAILH_SWITCH_SOCKET_KAILH_SWITCH_SOCKET")
      (footprint "eagle-import:KAILH_SWITCH_SOCKET_SWITCH_SOCKET")
      (libsource (lib "eagle-import") (part "KAILH_SWITCH_SOCKET_KAILH_SWITCH_SOCKET"))
    )
    (comp (ref "SWR4C3")
      (value "KAILH_SWITCH_SOCKET_KAILH_SWITCH_SOCKET")
      (footprint "eagle-import:KAILH_SWITCH_SOCKET_SWITCH_SOCKET")
      (libsource (lib "eagle-import") (part "KAILH_SWITCH_SOCKET_KAILH_SWITCH_SOCKET"))
    )
    (comp (ref "SWR4C4")
      (value "KAILH_SWITCH_SOCKET_KAILH_SWITCH_SOCKET")
      (footprint "eagle-import:KAILH_SWITCH_SOCKET_SWITCH_SOCKET")
      (libsource (lib "eagle-import") (part "KAILH_SWITCH_SOCKET_KAILH_SWITCH_SOCKET"))
    )
    (comp (ref "SWR5C1")
      (value "KAILH_SWITCH_SOCKET_KAILH_SWITCH_SOCKET")
      (footprint "eagle-import:KAILH_SWITCH_SOCKET_SWITCH_SOCKET")
      (libsource (lib "eagle-import") (part "KAILH_SWITCH_SOCKET_KAILH_SWITCH_SOCKET"))
    )
    (comp (ref "SWR5C2")
      (value "KAILH_SWITCH_SOCKET_KAILH_SWITCH_SOCKET")
      (footprint "eagle-import:KAILH_SWITCH_SOCKET_SWITCH_SOCKET")
      (libsource (lib "eagle-import") (part "KAILH_SWITCH_SOCKET_KAILH_SWITCH_SOCKET"))
    )
    (comp (ref "SWR5C3")
      (value "KAILH_SWITCH_SOCKET_KAILH_SWITCH_SOCKET")
      (footprint "eagle-import:KAILH_SWITCH_SOCKET_SWITCH_SOCKET")
      (libsource (lib "eagle-import") (part "KAILH_SWITCH_SOCKET_KAILH_SWITCH_SOCKET"))
    )
    (comp (ref "SWR5C4")
      (value "KAILH_SWITCH_SOCKET_KAILH_SWITCH_SOCKET")
      (footprint "eagle-import:KAILH_SWITCH_SOCKET_SWITCH_SOCKET")
      (libsource (lib "eagle-import") (part "KAILH_SWITCH_SOCKET_KAILH_SWITCH_SOCKET"))
    )
    (comp (ref "U$2")
      (value "OLED_OLED128")
      (footprint "eagle-import:OLED_LUL_UG-2864HSWEG01_1.3_WRAPAROUND")
      (libsource (lib "eagle-import") (part "OLED_OLED128"))
    )
    (comp (ref "U$7")
      (value "M2_SCREW_DEV")
      (footprint "eagle-import:M2_SCREW_FOOT")
      (libsource (lib "eagle-import") (part "M2_SCREW_DEV"))
    )
    (comp (ref "U$8")
      (value "M2_SCREW_DEV")
      (footprint "eagle-import:M2_SCREW_FOOT")
      (libsource (lib "eagle-import") (part "M2_SCREW_DEV"))
    )
    (comp (ref "U$9")
      (value "M2_SCREW_DEV")
      (footprint "eagle-import:M2_SCREW_FOOT")
      (libsource (lib "eagle-import") (part "M2_SCREW_DEV"))
    )
    (comp (ref "U$11")
      (value "M2_SCREW_DEV")
      (footprint "eagle-import:M2_SCREW_FOOT")
      (libsource (lib "eagle-import") (part "M2_SCREW_DEV"))
    )
    (comp (ref "U$12")
      (value "M2_SCREW_DEV")
      (footprint "eagle-import:M2_SCREW_FOOT")
      (libsource (lib "eagle-import") (part "M2_SCREW_DEV"))
    )
    (comp (ref "U$13")
      (value "M2_SCREW_DEV")
      (footprint "eagle-import:M2_SCREW_FOOT")
      (libsource (lib "eagle-import") (part "M2_SCREW_DEV"))
    )
    (comp (ref "U$14")
      (value "M2_SCREW_DEV")
      (footprint "eagle-import:M2_SCREW_FOOT")
      (libsource (lib "eagle-import") (part "M2_SCREW_DEV"))
    )
    (comp (ref "U$15")
      (value "M2_SCREW_DEV")
      (footprint "eagle-import:M2_SCREW_FOOT")
      (libsource (lib "eagle-import") (part "M2_SCREW_DEV"))
    )
    (comp (ref "U$16")
      (value "M2_SCREW_DEV")
      (footprint "eagle-import:M2_SCREW_FOOT")
      (libsource (lib "eagle-import") (part "M2_SCREW_DEV"))
    )
    (comp (ref "U$17")
      (value "M2_SCREW_DEV")
      (footprint "eagle-import:M2_SCREW_FOOT")
      (libsource (lib "eagle-import") (part "M2_SCREW_DEV"))
    )
    (comp (ref "U$20")
      (value "M2_SCREW_DEV")
      (footprint "eagle-import:M2_SCREW_FOOT")
      (libsource (lib "eagle-import") (part "M2_SCREW_DEV"))
    )
    (comp (ref "U$21")
      (value "M2_SCREW_DEV")
      (footprint "eagle-import:M2_SCREW_FOOT")
      (libsource (lib "eagle-import") (part "M2_SCREW_DEV"))
    )
    (comp (ref "U$22")
      (value "M2_SCREW_DEV")
      (footprint "eagle-import:M2_SCREW_FOOT")
      (libsource (lib "eagle-import") (part "M2_SCREW_DEV"))
    )
    (comp (ref "U1")
      (value "USBC_16P")
      (footprint "eagle-import:USBC_16P_FOOT")
      (libsource (lib "eagle-import") (part "USBC_16P"))
    )
    (comp (ref "U2")
      (value "USBC_16P")
      (footprint "eagle-import:USBC_16P_FOOT")
      (libsource (lib "eagle-import") (part "USBC_16P"))
    )
    (comp (ref "U3")
      (value "ESP32-S3FN8")
      (footprint "eagle-import:QFN40P700X700X90-57N")
      (fields (field (name "MF") "Espressif Systems"))
      (libsource (lib "eagle-import") (part "ESP32-S3FN8"))
    )
    (comp (ref "U19")
      (value "V_REG_TPS61040SMD")
      (footprint "eagle-import:SOT23-5")
      (libsource (lib "eagle-import") (part "V_REG_TPS61040SMD"))
    )
    (comp (ref "X1")
      (value "ANTENNA_U.FL")
      (footprint "eagle-import:U.FL")
      (libsource (lib "eagle-import") (part "ANTENNA_U.FL"))
    )
    (comp (ref "X2")
      (value "ANTENNA_U.FL")
      (footprint "eagle-import:U.FL")
      (libsource (lib "eagle-import") (part "ANTENNA_U.FL"))
    )
    (comp (ref "Y1")
      (value "16MHz_12pF")
      (footprint "eagle-import:CRYSTAL-SMD-3.2X2.5MM")
      (libsource (lib "eagle-import") (part "CRYSTAL-26MHZSMD-3.2X2.5"))
    )
  )
  (nets
    (net (code "1") (name "+3V3") (class "Default")
      (node (ref "BZ1") (pin "PLUS") (pinfunction "PLUS_PLUS") (pintype "bidirectional"))
      (node (ref "C11") (pin "2") (pinfunction "2_2") (pintype "passive"))
      (node (ref "C12") (pin "2") (pinfunction "2_2") (pintype "passive"))
      (node (ref "C13") (pin "2") (pinfunction "2_2") (pintype "passive"))
      (node (ref "C14") (pin "2") (pinfunction "2_2") (pintype "passive"))
      (node (ref "C15") (pin "2") (pinfunction "2_2") (pintype "passive"))
      (node (ref "C16") (pin "2") (pinfunction "2_2") (pintype "passive"))
      (node (ref "C17") (pin "2") (pinfunction "2_2") (pintype "passive"))
      (node (ref "C18") (pin "2") (pinfunction "2_2") (pintype "passive"))
      (node (ref "C19") (pin "2") (pinfunction "2_2") (pintype "passive"))
      (node (ref "C20") (pin "2") (pinfunction "2_2") (pintype "passive"))
      (node (ref "C21") (pin "2") (pinfunction "2_2") (pintype "passive"))
      (node (ref "C22") (pin "2") (pinfunction "2_2") (pintype "passive"))
      (node (ref "C23") (pin "2") (pinfunction "2_2") (pintype "passive"))
      (node (ref "C24") (pin "2") (pinfunction "2_2") (pintype "passive"))
      (node (ref "C25") (pin "2") (pinfunction "2_2") (pintype "passive"))
      (node (ref "C26") (pin "2") (pinfunction "2_2") (pintype "passive"))
      (node (ref "C27") (pin "1") (pinfunction "1_1") (pintype "passive"))
      (node (ref "C28") (pin "2") (pinfunction "2_2") (pintype "passive"))
      (node (ref "C33") (pin "2") (pinfunction "2_2") (pintype "passive"))
      (node (ref "C36") (pin "2") (pinfunction "2_2") (pintype "passive"))
      (node (ref "C37") (pin "2") (pinfunction "2_2") (pintype "passive"))
      (node (ref "C38") (pin "2") (pinfunction "2_2") (pintype "passive"))
      (node (ref "C39") (pin "2") (pinfunction "2_2") (pintype "passive"))
      (node (ref "C41") (pin "2") (pinfunction "2_2") (pintype "passive"))
      (node (ref "C42") (pin "2") (pinfunction "2_2") (pintype "passive"))
      (node (ref "C43") (pin "2") (pinfunction "2_2") (pintype "passive"))
      (node (ref "C44") (pin "2") (pinfunction "2_2") (pintype "passive"))
      (node (ref "C45") (pin "2") (pinfunction "2_2") (pintype "passive"))
      (node (ref "C5") (pin "2") (pinfunction "2_2") (pintype "passive"))
      (node (ref "C6") (pin "2") (pinfunction "2_2") (pintype "passive"))
      (node (ref "C7") (pin "2") (pinfunction "2_2") (pintype "passive"))
      (node (ref "D22") (pin "C") (pinfunction "C_C") (pintype "passive"))
      (node (ref "IC2") (pin "2") (pinfunction "VOUT_2") (pintype "output"))
      (node (ref "IC2") (pin "4") (pinfunction "VOUT_4") (pintype "output"))
      (node (ref "L2") (pin "1") (pinfunction "1_1") (pintype "passive"))
      (node (ref "LED_R1C1") (pin "VDD") (pinfunction "VDD_VDD") (pintype "power_in"))
      (node (ref "LED_R1C2") (pin "VDD") (pinfunction "VDD_VDD") (pintype "power_in"))
      (node (ref "LED_R1C3") (pin "VDD") (pinfunction "VDD_VDD") (pintype "power_in"))
      (node (ref "LED_R1C4") (pin "VDD") (pinfunction "VDD_VDD") (pintype "power_in"))
      (node (ref "LED_R2C1") (pin "VDD") (pinfunction "VDD_VDD") (pintype "power_in"))
      (node (ref "LED_R2C2") (pin "VDD") (pinfunction "VDD_VDD") (pintype "power_in"))
      (node (ref "LED_R2C3") (pin "VDD") (pinfunction "VDD_VDD") (pintype "power_in"))
      (node (ref "LED_R2C4") (pin "VDD") (pinfunction "VDD_VDD") (pintype "power_in"))
      (node (ref "LED_R3C1") (pin "VDD") (pinfunction "VDD_VDD") (pintype "power_in"))
      (node (ref "LED_R3C2") (pin "VDD") (pinfunction "VDD_VDD") (pintype "power_in"))
      (node (ref "LED_R3C3") (pin "VDD") (pinfunction "VDD_VDD") (pintype "power_in"))
      (node (ref "LED_R3C4") (pin "VDD") (pinfunction "VDD_VDD") (pintype "power_in"))
      (node (ref "LED_R4C1") (pin "VDD") (pinfunction "VDD_VDD") (pintype "power_in"))
      (node (ref "LED_R4C2") (pin "VDD") (pinfunction "VDD_VDD") (pintype "power_in"))
      (node (ref "LED_R4C3") (pin "VDD") (pinfunction "VDD_VDD") (pintype "power_in"))
      (node (ref "LED_R4C4") (pin "VDD") (pinfunction "VDD_VDD") (pintype "power_in"))
      (node (ref "LED_R5C1") (pin "VDD") (pinfunction "VDD_VDD") (pintype "power_in"))
      (node (ref "LED_R5C2") (pin "VDD") (pinfunction "VDD_VDD") (pintype "power_in"))
      (node (ref "LED_R5C3") (pin "VDD") (pinfunction "VDD_VDD") (pintype "power_in"))
      (node (ref "LED_R5C4") (pin "VDD") (pinfunction "VDD_VDD") (pintype "power_in"))
      (node (ref "R11") (pin "1") (pinfunction "1_1") (pintype "passive"))
      (node (ref "R12") (pin "2") (pinfunction "2_2") (pintype "passive"))
      (node (ref "R16") (pin "2") (pinfunction "2_2") (pintype "passive"))
      (node (ref "R2") (pin "1") (pinfunction "1_1") (pintype "passive"))
      (node (ref "SD1") (pin "4") (pinfunction "VDD_4") (pintype "power_in"))
      (node (ref "SH1") (pin "3") (pinfunction "3_3") (pintype "passive"))
      (node (ref "U$2") (pin "4") (pinfunction "VDD_4") (pintype "bidirectional"))
      (node (ref "U19") (pin "4") (pinfunction "EN_4") (pintype "bidirectional"))
      (node (ref "U19") (pin "5") (pinfunction "VIN_5") (pintype "bidirectional"))
      (node (ref "U3") (pin "2") (pinfunction "VDD3P3_2") (pintype "power_in"))
      (node (ref "U3") (pin "20") (pinfunction "VDD3P3_RTC_20") (pintype "power_in"))
      (node (ref "U3") (pin "3") (pinfunction "VDD3P3_3") (pintype "power_in"))
      (node (ref "U3") (pin "46") (pinfunction "VDD3P3_CPU_46") (pintype "power_in"))
      (node (ref "U3") (pin "55") (pinfunction "VDDA1_55") (pintype "power_in"))
      (node (ref "U3") (pin "56") (pinfunction "VDDA2_56") (pintype "power_in"))
    )
    (net (code "2") (name "/CARD_DET") (class "Default")
      (node (ref "SD1") (pin "9") (pinfunction "~{CARD}_9") (pintype "passive"))
      (node (ref "U3") (pin "11") (pinfunction "GPIO6_11") (pintype "bidirectional"))
    )
    (net (code "3") (name "/SD_CLK") (class "Default")
      (node (ref "SD1") (pin "5") (pinfunction "CLK(SCLK)_5") (pintype "input"))
      (node (ref "U3") (pin "13") (pinfunction "GPIO8_13") (pintype "bidirectional"))
    )
    (net (code "4") (name "/SD_CMD") (class "Default")
      (node (ref "SD1") (pin "3") (pinfunction "CMD(DI)_3") (pintype "bidirectional"))
      (node (ref "U3") (pin "14") (pinfunction "GPIO9_14") (pintype "bidirectional"))
    )
    (net (code "5") (name "/SD_D0") (class "Default")
      (node (ref "SD1") (pin "7") (pinfunction "DAT0(DO)_7") (pintype "bidirectional"))
      (node (ref "U3") (pin "12") (pinfunction "GPIO7_12") (pintype "bidirectional"))
    )
    (net (code "6") (name "/USB_DN") (class "Default")
      (node (ref "U2") (pin "A7") (pinfunction "DN1_A7") (pintype "bidirectional"))
      (node (ref "U2") (pin "B7") (pinfunction "DN2_B7") (pintype "bidirectional"))
      (node (ref "U3") (pin "25") (pinfunction "GPIO19_25") (pintype "bidirectional"))
    )
    (net (code "7") (name "/USB_DP") (class "Default")
      (node (ref "U2") (pin "A6") (pinfunction "DP1_A6") (pintype "bidirectional"))
      (node (ref "U2") (pin "B6") (pinfunction "DP2_B6") (pintype "bidirectional"))
      (node (ref "U3") (pin "26") (pinfunction "GPIO20_26") (pintype "bidirectional"))
    )
    (net (code "8") (name "/VDD_SPI") (class "Default")
      (node (ref "U3") (pin "29") (pinfunction "VDD_SPI_29") (pintype "power_in"))
    )
    (net (code "9") (name "12V") (class "Default")
      (node (ref "C31") (pin "2") (pinfunction "2_2") (pintype "passive"))
      (node (ref "C35") (pin "2") (pinfunction "2_2") (pintype "passive"))
      (node (ref "C40") (pin "2") (pinfunction "2_2") (pintype "passive"))
      (node (ref "C46") (pin "2") (pinfunction "2_2") (pintype "passive"))
      (node (ref "D1") (pin "C") (pinfunction "C_C") (pintype "passive"))
      (node (ref "R7") (pin "1") (pinfunction "1_1") (pintype "passive"))
      (node (ref "U$2") (pin "11") (pinfunction "VCC2_11") (pintype "bidirectional"))
      (node (ref "U$2") (pin "2") (pinfunction "VCC_2") (pintype "bidirectional"))
    )
    (net (code "10") (name "AUX_DN") (class "Default")
      (node (ref "U1") (pin "A7") (pinfunction "DN1_A7") (pintype "bidirectional"))
      (node (ref "U1") (pin "B7") (pinfunction "DN2_B7") (pintype "bidirectional"))
      (node (ref "U3") (pin "21") (pinfunction "XTAL_32K_P_21") (pintype "bidirectional"))
    )
    (net (code "11") (name "AUX_DP") (class "Default")
      (node (ref "U1") (pin "A6") (pinfunction "DP1_A6") (pintype "bidirectional"))
      (node (ref "U1") (pin "B6") (pinfunction "DP2_B6") (pintype "bidirectional"))
      (node (ref "U3") (pin "22") (pinfunction "XTAL_32K_N_22") (pintype "bidirectional"))
    )
    (net (code "12") (name "COL0") (class "Default")
      (node (ref "SWR1C1") (pin "1") (pinfunction "2_1") (pintype "passive"))
      (node (ref "SWR2C1") (pin "1") (pinfunction "2_1") (pintype "passive"))
      (node (ref "SWR3C1") (pin "1") (pinfunction "2_1") (pintype "passive"))
      (node (ref "SWR4C1") (pin "1") (pinfunction "2_1") (pintype "passive"))
      (node (ref "SWR5C1") (pin "1") (pinfunction "2_1") (pintype "passive"))
      (node (ref "U3") (pin "48") (pinfunction "MTMS_48") (pintype "bidirectional"))
    )
    (net (code "13") (name "COL1") (class "Default")
      (node (ref "SWR1C2") (pin "1") (pinfunction "2_1") (pintype "passive"))
      (node (ref "SWR2C2") (pin "1") (pinfunction "2_1") (pintype "passive"))
      (node (ref "SWR3C2") (pin "1") (pinfunction "2_1") (pintype "passive"))
      (node (ref "SWR4C2") (pin "1") (pinfunction "2_1") (pintype "passive"))
      (node (ref "SWR5C2") (pin "1") (pinfunction "2_1") (pintype "passive"))
      (node (ref "U3") (pin "47") (pinfunction "MTDI_47") (pintype "bidirectional"))
    )
    (net (code "14") (name "COL2") (class "Default")
      (node (ref "SWR1C3") (pin "1") (pinfunction "2_1") (pintype "passive"))
      (node (ref "SWR2C3") (pin "1") (pinfunction "2_1") (pintype "passive"))
      (node (ref "SWR3C3") (pin "1") (pinfunction "2_1") (pintype "passive"))
      (node (ref "SWR4C3") (pin "1") (pinfunction "2_1") (pintype "passive"))
      (node (ref "SWR5C3") (pin "1") (pinfunction "2_1") (pintype "passive"))
      (node (ref "U3") (pin "44") (pinfunction "MTCK_44") (pintype "bidirectional"))
    )
    (net (code "15") (name "COL3") (class "Default")
      (node (ref "SWR1C4") (pin "1") (pinfunction "2_1") (pintype "passive"))
      (node (ref "SWR2C4") (pin "1") (pinfunction "2_1") (pintype "passive"))
      (node (ref "SWR3C4") (pin "1") (pinfunction "2_1") (pintype "passive"))
      (node (ref "SWR4C4") (pin "1") (pinfunction "2_1") (pintype "passive"))
      (node (ref "SWR5C4") (pin "1") (pinfunction "2_1") (pintype "passive"))
      (node (ref "U3") (pin "43") (pinfunction "GPIO38_43") (pintype "bidirectional"))
    )
    (net (code "16") (name "DC") (class "Default")
      (node (ref "U$2") (pin "8") (pinfunction "DC_8") (pintype "bidirectional"))
      (node (ref "U3") (pin "17") (pinfunction "GPIO12_17") (pintype "bidirectional"))
    )
    (net (code "17") (name "GND") (class "Default")
      (node (ref "C1") (pin "1") (pinfunction "1_1") (pintype "passive"))
      (node (ref "C10") (pin "1") (pinfunction "1_1") (pintype "passive"))
      (node (ref "C11") (pin "1") (pinfunction "1_1") (pintype "passive"))
      (node (ref "C12") (pin "1") (pinfunction "1_1") (pintype "passive"))
      (node (ref "C13") (pin "1") (pinfunction "1_1") (pintype "passive"))
      (node (ref "C14") (pin "1") (pinfunction "1_1") (pintype "passive"))
      (node (ref "C15") (pin "1") (pinfunction "1_1") (pintype "passive"))
      (node (ref "C16") (pin "1") (pinfunction "1_1") (pintype "passive"))
      (node (ref "C17") (pin "1") (pinfunction "1_1") (pintype "passive"))
      (node (ref "C18") (pin "1") (pinfunction "1_1") (pintype "passive"))
      (node (ref "C19") (pin "1") (pinfunction "1_1") (pintype "passive"))
      (node (ref "C2") (pin "1") (pinfunction "1_1") (pintype "passive"))
      (node (ref "C20") (pin "1") (pinfunction "1_1") (pintype "passive"))
      (node (ref "C21") (pin "1") (pinfunction "1_1") (pintype "passive"))
      (node (ref "C22") (pin "1") (pinfunction "1_1") (pintype "passive"))
      (node (ref "C23") (pin "1") (pinfunction "1_1") (pintype "passive"))
      (node (ref "C24") (pin "1") (pinfunction "1_1") (pintype "passive"))
      (node (ref "C25") (pin "1") (pinfunction "1_1") (pintype "passive"))
      (node (ref "C26") (pin "1") (pinfunction "1_1") (pintype "passive"))
      (node (ref "C27") (pin "2") (pinfunction "2_2") (pintype "passive"))
      (node (ref "C28") (pin "1") (pinfunction "1_1") (pintype "passive"))
      (node (ref "C29") (pin "1") (pinfunction "1_1") (pintype "passive"))
      (node (ref "C3") (pin "2") (pinfunction "2_2") (pintype "passive"))
      (node (ref "C31") (pin "1") (pinfunction "1_1") (pintype "passive"))
      (node (ref "C33") (pin "1") (pinfunction "1_1") (pintype "passive"))
      (node (ref "C34") (pin "1") (pinfunction "1_1") (pintype "passive"))
      (node (ref "C36") (pin "1") (pinfunction "1_1") (pintype "passive"))
      (node (ref "C37") (pin "1") (pinfunction "1_1") (pintype "passive"))
      (node (ref "C38") (pin "1") (pinfunction "1_1") (pintype "passive"))
      (node (ref "C39") (pin "1") (pinfunction "1_1") (pintype "passive"))
      (node (ref "C4") (pin "2") (pinfunction "2_2") (pintype "passive"))
      (node (ref "C40") (pin "1") (pinfunction "1_1") (pintype "passive"))
      (node (ref "C41") (pin "1") (pinfunction "1_1") (pintype "passive"))
      (node (ref "C42") (pin "1") (pinfunction "1_1") (pintype "passive"))
      (node (ref "C43") (pin "1") (pinfunction "1_1") (pintype "passive"))
      (node (ref "C44") (pin "1") (pinfunction "1_1") (pintype "passive"))
      (node (ref "C45") (pin "1") (pinfunction "1_1") (pintype "passive"))
      (node (ref "C46") (pin "1") (pinfunction "1_1") (pintype "passive"))
      (node (ref "C5") (pin "1") (pinfunction "1_1") (pintype "passive"))
      (node (ref "C6") (pin "1") (pinfunction "1_1") (pintype "passive"))
      (node (ref "C7") (pin "1") (pinfunction "1_1") (pintype "passive"))
      (node (ref "C8") (pin "2") (pinfunction "2_2") (pintype "passive"))
      (node (ref "C9") (pin "1") (pinfunction "1_1") (pintype "passive"))
      (node (ref "IC2") (pin "1") (pinfunction "GND_1") (pintype "power_in"))
      (node (ref "LED_R1C1") (pin "GND") (pinfunction "GND_GND") (pintype "power_in"))
      (node (ref "LED_R1C2") (pin "GND") (pinfunction "GND_GND") (pintype "power_in"))
      (node (ref "LED_R1C3") (pin "GND") (pinfunction "GND_GND") (pintype "power_in"))
      (node (ref "LED_R1C4") (pin "GND") (pinfunction "GND_GND") (pintype "power_in"))
      (node (ref "LED_R2C1") (pin "GND") (pinfunction "GND_GND") (pintype "power_in"))
      (node (ref "LED_R2C2") (pin "GND") (pinfunction "GND_GND") (pintype "power_in"))
      (node (ref "LED_R2C3") (pin "GND") (pinfunction "GND_GND") (pintype "power_in"))
      (node (ref "LED_R2C4") (pin "GND") (pinfunction "GND_GND") (pintype "power_in"))
      (node (ref "LED_R3C1") (pin "GND") (pinfunction "GND_GND") (pintype "power_in"))
      (node (ref "LED_R3C2") (pin "GND") (pinfunction "GND_GND") (pintype "power_in"))
      (node (ref "LED_R3C3") (pin "GND") (pinfunction "GND_GND") (pintype "power_in"))
      (node (ref "LED_R3C4") (pin "GND") (pinfunction "GND_GND") (pintype "power_in"))
      (node (ref "LED_R4C1") (pin "GND") (pinfunction "GND_GND") (pintype "power_in"))
      (node (ref "LED_R4C2") (pin "GND") (pinfunction "GND_GND") (pintype "power_in"))
      (node (ref "LED_R4C3") (pin "GND") (pinfunction "GND_GND") (pintype "power_in"))
      (node (ref "LED_R4C4") (pin "GND") (pinfunction "GND_GND") (pintype "power_in"))
      (node (ref "LED_R5C1") (pin "GND") (pinfunction "GND_GND") (pintype "power_in"))
      (node (ref "LED_R5C2") (pin "GND") (pinfunction "GND_GND") (pintype "power_in"))
      (node (ref "LED_R5C3") (pin "GND") (pinfunction "GND_GND") (pintype "power_in"))
      (node (ref "LED_R5C4") (pin "GND") (pinfunction "GND_GND") (pintype "power_in"))
      (node (ref "Q1") (pin "2") (pinfunction "S_2") (pintype "passive"))
      (node (ref "R1") (pin "2") (pinfunction "2_2") (pintype "passive"))
      (node (ref "R10") (pin "2") (pinfunction "2_2") (pintype "passive"))
      (node (ref "R17") (pin "1") (pinfunction "1_1") (pintype "passive"))
      (node (ref "R18") (pin "1") (pinfunction "1_1") (pintype "passive"))
      (node (ref "R19") (pin "1") (pinfunction "1_1") (pintype "passive"))
      (node (ref "R4") (pin "1") (pinfunction "1_1") (pintype "passive"))
      (node (ref "R5") (pin "1") (pinfunction "1_1") (pintype "passive"))
      (node (ref "R6") (pin "1") (pinfunction "1_1") (pintype "passive"))
      (node (ref "R9") (pin "2") (pinfunction "2_2") (pintype "passive"))
      (node (ref "SD1") (pin "6") (pinfunction "VSS_6") (pintype "power_in"))
      (node (ref "SD1") (pin "S1") (pinfunction "S1_S1") (pintype "passive"))
      (node (ref "SD1") (pin "S2") (pinfunction "S2_S2") (pintype "passive"))
      (node (ref "SD1") (pin "S3") (pinfunction "S3_S3") (pintype "passive"))
      (node (ref "SD1") (pin "S4") (pinfunction "S4_S4") (pintype "passive"))
      (node (ref "SH1") (pin "2") (pinfunction "2_2") (pintype "passive"))
      (node (ref "SH1") (pin "FIT@1") (pinfunction "11_FIT@1") (pintype "passive"))
      (node (ref "SH1") (pin "FIT@2") (pinfunction "12_FIT@2") (pintype "passive"))
      (node (ref "SW1") (pin "A") (pinfunction "P_A") (pintype "passive"))
      (node (ref "SW1") (pin "A'") (pinfunction "P1_A'") (pintype "passive"))
      (node (ref "SW2") (pin "A") (pinfunction "P_A") (pintype "passive"))
      (node (ref "SW2") (pin "A'") (pinfunction "P1_A'") (pintype "passive"))
      (node (ref "SW21") (pin "C") (pinfunction "C_C") (pintype "passive"))
      (node (ref "SW21") (pin "E") (pinfunction "2_E") (pintype "passive"))
      (node (ref "SW22") (pin "C") (pinfunction "C_C") (pintype "passive"))
      (node (ref "SW22") (pin "E") (pinfunction "2_E") (pintype "passive"))
      (node (ref "SW3") (pin "P$1") (pinfunction "1_P$1") (pintype "bidirectional"))
      (node (ref "SW3") (pin "P$4") (pinfunction "4_P$4") (pintype "bidirectional"))
      (node (ref "SW4") (pin "P$1") (pinfunction "1_P$1") (pintype "bidirectional"))
      (node (ref "SW4") (pin "P$4") (pinfunction "4_P$4") (pintype "bidirectional"))
      (node (ref "U$2") (pin "1") (pinfunction "GND_1") (pintype "bidirectional"))
      (node (ref "U$2") (pin "12") (pinfunction "GND2_12") (pintype "bidirectional"))
      (node (ref "U$2") (pin "31") (pinfunction "SHIELD_31") (pintype "bidirectional"))
      (node (ref "U$2") (pin "32") (pinfunction "SHIELD_32") (pintype "bidirectional"))
      (node (ref "U1") (pin "A1B12") (pinfunction "GND_A1B12") (pintype "bidirectional"))
      (node (ref "U1") (pin "B11A12") (pinfunction "GND_B11A12") (pintype "bidirectional"))
      (node (ref "U1") (pin "P$13") (pinfunction "GND_P$13") (pintype "bidirectional"))
      (node (ref "U1") (pin "P$14") (pinfunction "GND_P$14") (pintype "bidirectional"))
      (node (ref "U1") (pin "P$15") (pinfunction "GND_P$15") (pintype "bidirectional"))
      (node (ref "U1") (pin "P$16") (pinfunction "GND_P$16") (pintype "bidirectional"))
      (node (ref "U19") (pin "2") (pinfunction "GND_2") (pintype "bidirectional"))
      (node (ref "U2") (pin "A1B12") (pinfunction "GND_A1B12") (pintype "bidirectional"))
      (node (ref "U2") (pin "B11A12") (pinfunction "GND_B11A12") (pintype "bidirectional"))
      (node (ref "U2") (pin "P$13") (pinfunction "GND_P$13") (pintype "bidirectional"))
      (node (ref "U2") (pin "P$14") (pinfunction "GND_P$14") (pintype "bidirectional"))
      (node (ref "U2") (pin "P$15") (pinfunction "GND_P$15") (pintype "bidirectional"))
      (node (ref "U2") (pin "P$16") (pinfunction "GND_P$16") (pintype "bidirectional"))
      (node (ref "U3") (pin "57") (pinfunction "GND_57") (pintype "power_in"))
      (node (ref "X1") (pin "1") (pinfunction "GND_1") (pintype "passive"))
      (node (ref "X1") (pin "2") (pinfunction "GND_2") (pintype "passive"))
      (node (ref "X2") (pin "1") (pinfunction "GND_1") (pintype "passive"))
      (node (ref "X2") (pin "2") (pinfunction "GND_2") (pintype "passive"))
      (node (ref "Y1") (pin "2") (pinfunction "3_2") (pintype "passive"))
      (node (ref "Y1") (pin "4") (pinfunction "3_4") (pintype "passive"))
    )
    (net (code "18") (name "HEHE") (class "Default")
      (node (ref "SH1") (pin "4") (pinfunction "4_4") (pintype "passive"))
      (node (ref "U3") (pin "27") (pinfunction "GPIO21_27") (pintype "bidirectional"))
    )
    (net (code "19") (name "MOSI") (class "Default")
      (node (ref "U$2") (pin "10") (pinfunction "D1_10") (pintype "bidirectional"))
      (node (ref "U3") (pin "15") (pinfunction "GPIO10_15") (pintype "bidirectional"))
    )
    (net (code "20") (name "Net-(IC2-VIN)") (class "Default")
      (node (ref "C29") (pin "2") (pinfunction "2_2") (pintype "passive"))
      (node (ref "IC2") (pin "3") (pinfunction "VIN_3") (pintype "input"))
      (node (ref "JP1") (pin "2") (pinfunction "2_2") (pintype "passive"))
      (node (ref "JP2") (pin "2") (pinfunction "2_2") (pintype "passive"))
      (node (ref "SH1") (pin "1") (pinfunction "1_1") (pintype "passive"))
      (node (ref "U1") (pin "A4B9") (pinfunction "VBUS_A4B9") (pintype "bidirectional"))
      (node (ref "U1") (pin "B4A9") (pinfunction "VBUS_B4A9") (pintype "bidirectional"))
    )
    (net (code "21") (name "Net-(JP1-Pad1)") (class "Default")
      (node (ref "JP1") (pin "1") (pinfunction "1_1") (pintype "passive"))
      (node (ref "JP2") (pin "1") (pinfunction "1_1") (pintype "passive"))
      (node (ref "U2") (pin "A4B9") (pinfunction "VBUS_A4B9") (pintype "bidirectional"))
      (node (ref "U2") (pin "B4A9") (pinfunction "VBUS_B4A9") (pintype "bidirectional"))
    )
    (net (code "22") (name "Net-(LED_R1C1-DI)") (class "Default")
      (node (ref "LED_R1C1") (pin "DIN") (pinfunction "DI_DIN") (pintype "input"))
      (node (ref "LED_R1C2") (pin "DOUT") (pinfunction "DO_DOUT") (pintype "output"))
    )
    (net (code "23") (name "Net-(LED_R1C1-DO)") (class "Default")
      (node (ref "LED_R1C1") (pin "DOUT") (pinfunction "DO_DOUT") (pintype "output"))
      (node (ref "LED_R2C1") (pin "DIN") (pinfunction "DI_DIN") (pintype "input"))
    )
    (net (code "24") (name "Net-(LED_R1C2-DI)") (class "Default")
      (node (ref "LED_R1C2") (pin "DIN") (pinfunction "DI_DIN") (pintype "input"))
      (node (ref "LED_R1C3") (pin "DOUT") (pinfunction "DO_DOUT") (pintype "output"))
    )
    (net (code "25") (name "Net-(LED_R1C3-DI)") (class "Default")
      (node (ref "LED_R1C3") (pin "DIN") (pinfunction "DI_DIN") (pintype "input"))
      (node (ref "LED_R1C4") (pin "DOUT") (pinfunction "DO_DOUT") (pintype "output"))
    )
    (net (code "26") (name "Net-(LED_R1C4-DI)") (class "Default")
      (node (ref "LED_R1C4") (pin "DIN") (pinfunction "DI_DIN") (pintype "input"))
      (node (ref "R5") (pin "2") (pinfunction "2_2") (pintype "passive"))
      (node (ref "U3") (pin "52") (pinfunction "GPIO46_52") (pintype "bidirectional"))
    )
    (net (code "27") (name "Net-(LED_R2C1-DO)") (class "Default")
      (node (ref "LED_R2C1") (pin "DOUT") (pinfunction "DO_DOUT") (pintype "output"))
      (node (ref "LED_R2C2") (pin "DIN") (pinfunction "DI_DIN") (pintype "input"))
    )
    (net (code "28") (name "Net-(LED_R2C2-DO)") (class "Default")
      (node (ref "LED_R2C2") (pin "DOUT") (pinfunction "DO_DOUT") (pintype "output"))
      (node (ref "LED_R2C3") (pin "DIN") (pinfunction "DI_DIN") (pintype "input"))
    )
    (net (code "29") (name "Net-(LED_R2C3-DO)") (class "Default")
      (node (ref "LED_R2C3") (pin "DOUT") (pinfunction "DO_DOUT") (pintype "output"))
      (node (ref "LED_R2C4") (pin "DIN") (pinfunction "DI_DIN") (pintype "input"))
    )
    (net (code "30") (name "Net-(LED_R2C4-DO)") (class "Default")
      (node (ref "LED_R2C4") (pin "DOUT") (pinfunction "DO_DOUT") (pintype "output"))
      (node (ref "LED_R3C4") (pin "DIN") (pinfunction "DI_DIN") (pintype "input"))
    )
    (net (code "31") (name "Net-(LED_R3C1-DI)") (class "Default")
      (node (ref "LED_R3C1") (pin "DIN") (pinfunction "DI_DIN") (pintype "input"))
      (node (ref "LED_R3C2") (pin "DOUT") (pinfunction "DO_DOUT") (pintype "output"))
    )
    (net (code "32") (name "Net-(LED_R3C1-DO)") (class "Default")
      (node (ref "LED_R3C1") (pin "DOUT") (pinfunction "DO_DOUT") (pintype "output"))
      (node (ref "LED_R4C1") (pin "DIN") (pinfunction "DI_DIN") (pintype "input"))
    )
    (net (code "33") (name "Net-(LED_R3C2-DI)") (class "Default")
      (node (ref "LED_R3C2") (pin "DIN") (pinfunction "DI_DIN") (pintype "input"))
      (node (ref "LED_R3C3") (pin "DOUT") (pinfunction "DO_DOUT") (pintype "output"))
    )
    (net (code "34") (name "Net-(LED_R3C3-DI)") (class "Default")
      (node (ref "LED_R3C3") (pin "DIN") (pinfunction "DI_DIN") (pintype "input"))
      (node (ref "LED_R3C4") (pin "DOUT") (pinfunction "DO_DOUT") (pintype "output"))
    )
    (net (code "35") (name "Net-(LED_R4C1-DO)") (class "Default")
      (node (ref "LED_R4C1") (pin "DOUT") (pinfunction "DO_DOUT") (pintype "output"))
      (node (ref "LED_R4C2") (pin "DIN") (pinfunction "DI_DIN") (pintype "input"))
    )
    (net (code "36") (name "Net-(LED_R4C2-DO)") (class "Default")
      (node (ref "LED_R4C2") (pin "DOUT") (pinfunction "DO_DOUT") (pintype "output"))
      (node (ref "LED_R4C3") (pin "DIN") (pinfunction "DI_DIN") (pintype "input"))
    )
    (net (code "37") (name "Net-(LED_R4C3-DO)") (class "Default")
      (node (ref "LED_R4C3") (pin "DOUT") (pinfunction "DO_DOUT") (pintype "output"))
      (node (ref "LED_R4C4") (pin "DIN") (pinfunction "DI_DIN") (pintype "input"))
    )
    (net (code "38") (name "Net-(LED_R4C4-DO)") (class "Default")
      (node (ref "LED_R4C4") (pin "DOUT") (pinfunction "DO_DOUT") (pintype "output"))
      (node (ref "LED_R5C4") (pin "DIN") (pinfunction "DI_DIN") (pintype "input"))
    )
    (net (code "39") (name "Net-(LED_R5C1-DI)") (class "Default")
      (node (ref "LED_R5C1") (pin "DIN") (pinfunction "DI_DIN") (pintype "input"))
      (node (ref "LED_R5C2") (pin "DOUT") (pinfunction "DO_DOUT") (pintype "output"))
    )
    (net (code "40") (name "Net-(LED_R5C2-DI)") (class "Default")
      (node (ref "LED_R5C2") (pin "DIN") (pinfunction "DI_DIN") (pintype "input"))
      (node (ref "LED_R5C3") (pin "DOUT") (pinfunction "DO_DOUT") (pintype "output"))
    )
    (net (code "41") (name "Net-(LED_R5C3-DI)") (class "Default")
      (node (ref "LED_R5C3") (pin "DIN") (pinfunction "DI_DIN") (pintype "input"))
      (node (ref "LED_R5C4") (pin "DOUT") (pinfunction "DO_DOUT") (pintype "output"))
    )
    (net (code "42") (name "Net-(Q1-D)") (class "Default")
      (node (ref "BZ1") (pin "MINUS") (pinfunction "MINUS_MINUS") (pintype "bidirectional"))
      (node (ref "D22") (pin "A") (pinfunction "A_A") (pintype "passive"))
      (node (ref "Q1") (pin "3") (pinfunction "D_3") (pintype "passive"))
    )
    (net (code "43") (name "Net-(Q1-G)") (class "Default")
      (node (ref "Q1") (pin "1") (pinfunction "G_1") (pintype "passive"))
      (node (ref "R19") (pin "2") (pinfunction "2_2") (pintype "passive"))
      (node (ref "SH1") (pin "8") (pinfunction "8_8") (pintype "passive"))
      (node (ref "U3") (pin "39") (pinfunction "GPIO34_39") (pintype "bidirectional"))
    )
    (net (code "44") (name "Net-(R8-Pad2)") (class "Default")
      (node (ref "R8") (pin "2") (pinfunction "2_2") (pintype "passive"))
      (node (ref "SW22") (pin "A") (pinfunction "A_A") (pintype "passive"))
    )
    (net (code "45") (name "Net-(R13-Pad2)") (class "Default")
      (node (ref "R13") (pin "2") (pinfunction "2_2") (pintype "passive"))
      (node (ref "SW22") (pin "B") (pinfunction "B_B") (pintype "passive"))
    )
    (net (code "46") (name "Net-(R14-Pad2)") (class "Default")
      (node (ref "R14") (pin "2") (pinfunction "2_2") (pintype "passive"))
      (node (ref "SW21") (pin "A") (pinfunction "A_A") (pintype "passive"))
    )
    (net (code "47") (name "Net-(R15-Pad2)") (class "Default")
      (node (ref "R15") (pin "2") (pinfunction "2_2") (pintype "passive"))
      (node (ref "SW21") (pin "B") (pinfunction "B_B") (pintype "passive"))
    )
    (net (code "48") (name "Net-(SD1-CD{slash}DAT3(~{CS}))") (class "Default")
      (node (ref "R11") (pin "2") (pinfunction "2_2") (pintype "passive"))
      (node (ref "SD1") (pin "2") (pinfunction "CD/DAT3(~{CS})_2") (pintype "bidirectional"))
    )
    (net (code "49") (name "Net-(SW1-S)") (class "Default")
      (node (ref "SW1") (pin "B") (pinfunction "S_B") (pintype "passive"))
      (node (ref "SW1") (pin "B'") (pinfunction "S1_B'") (pintype "passive"))
      (node (ref "U3") (pin "23") (pinfunction "GPIO17_23") (pintype "bidirectional"))
    )
    (net (code "50") (name "Net-(SW2-S)") (class "Default")
      (node (ref "SW2") (pin "B") (pinfunction "S_B") (pintype "passive"))
      (node (ref "SW2") (pin "B'") (pinfunction "S1_B'") (pintype "passive"))
      (node (ref "U3") (pin "24") (pinfunction "GPIO18_24") (pintype "bidirectional"))
    )
    (net (code "51") (name "Net-(SW3-2)") (class "Default")
      (node (ref "C4") (pin "1") (pinfunction "1_1") (pintype "passive"))
      (node (ref "JP4") (pin "1") (pinfunction "1_1") (pintype "passive"))
      (node (ref "R2") (pin "2") (pinfunction "2_2") (pintype "passive"))
      (node (ref "SW3") (pin "P$2") (pinfunction "2_P$2") (pintype "bidirectional"))
      (node (ref "SW3") (pin "P$3") (pinfunction "3_P$3") (pintype "bidirectional"))
      (node (ref "U3") (pin "4") (pinfunction "CHIP_PU_4") (pintype "input"))
    )
    (net (code "52") (name "Net-(SW21B-1)") (class "Default")
      (node (ref "JP4") (pin "2") (pinfunction "2_2") (pintype "passive"))
      (node (ref "R16") (pin "1") (pinfunction "1_1") (pintype "passive"))
      (node (ref "SW21") (pin "D") (pinfunction "1_D") (pintype "passive"))
      (node (ref "U3") (pin "8") (pinfunction "GPIO3_8") (pintype "bidirectional"))
    )
    (net (code "53") (name "Net-(SW22B-1)") (class "Default")
      (node (ref "SW22") (pin "D") (pinfunction "1_D") (pintype "passive"))
      (node (ref "SW4") (pin "P$2") (pinfunction "2_P$2") (pintype "bidirectional"))
      (node (ref "SW4") (pin "P$3") (pinfunction "3_P$3") (pintype "bidirectional"))
      (node (ref "U3") (pin "5") (pinfunction "GPIO0_5") (pintype "bidirectional"))
    )
    (net (code "54") (name "Net-(SWR1C1-1)") (class "Default")
      (node (ref "D2") (pin "A") (pinfunction "A_A") (pintype "passive"))
      (node (ref "SWR1C1") (pin "2") (pinfunction "1_2") (pintype "passive"))
    )
    (net (code "55") (name "Net-(SWR1C2-1)") (class "Default")
      (node (ref "D3") (pin "A") (pinfunction "A_A") (pintype "passive"))
      (node (ref "SWR1C2") (pin "2") (pinfunction "1_2") (pintype "passive"))
    )
    (net (code "56") (name "Net-(SWR1C3-1)") (class "Default")
      (node (ref "D4") (pin "A") (pinfunction "A_A") (pintype "passive"))
      (node (ref "SWR1C3") (pin "2") (pinfunction "1_2") (pintype "passive"))
    )
    (net (code "57") (name "Net-(SWR1C4-1)") (class "Default")
      (node (ref "D5") (pin "A") (pinfunction "A_A") (pintype "passive"))
      (node (ref "SWR1C4") (pin "2") (pinfunction "1_2") (pintype "passive"))
    )
    (net (code "58") (name "Net-(SWR2C1-1)") (class "Default")
      (node (ref "D6") (pin "A") (pinfunction "A_A") (pintype "passive"))
      (node (ref "SWR2C1") (pin "2") (pinfunction "1_2") (pintype "passive"))
    )
    (net (code "59") (name "Net-(SWR2C2-1)") (class "Default")
      (node (ref "D7") (pin "A") (pinfunction "A_A") (pintype "passive"))
      (node (ref "SWR2C2") (pin "2") (pinfunction "1_2") (pintype "passive"))
    )
    (net (code "60") (name "Net-(SWR2C3-1)") (class "Default")
      (node (ref "D8") (pin "A") (pinfunction "A_A") (pintype "passive"))
      (node (ref "SWR2C3") (pin "2") (pinfunction "1_2") (pintype "passive"))
    )
    (net (code "61") (name "Net-(SWR2C4-1)") (class "Default")
      (node (ref "D9") (pin "A") (pinfunction "A_A") (pintype "passive"))
      (node (ref "SWR2C4") (pin "2") (pinfunction "1_2") (pintype "passive"))
    )
    (net (code "62") (name "Net-(SWR3C1-1)") (class "Default")
      (node (ref "D13") (pin "A") (pinfunction "A_A") (pintype "passive"))
      (node (ref "SWR3C1") (pin "2") (pinfunction "1_2") (pintype "passive"))
    )
    (net (code "63") (name "Net-(SWR3C2-1)") (class "Default")
      (node (ref "D12") (pin "A") (pinfunction "A_A") (pintype "passive"))
      (node (ref "SWR3C2") (pin "2") (pinfunction "1_2") (pintype "passive"))
    )
    (net (code "64") (name "Net-(SWR3C3-1)") (class "Default")
      (node (ref "D11") (pin "A") (pinfunction "A_A") (pintype "passive"))
      (node (ref "SWR3C3") (pin "2") (pinfunction "1_2") (pintype "passive"))
    )
    (net (code "65") (name "Net-(SWR3C4-1)") (class "Default")
      (node (ref "D10") (pin "A") (pinfunction "A_A") (pintype "passive"))
      (node (ref "SWR3C4") (pin "2") (pinfunction "1_2") (pintype "passive"))
    )
    (net (code "66") (name "Net-(SWR4C1-1)") (class "Default")
      (node (ref "D14") (pin "A") (pinfunction "A_A") (pintype "passive"))
      (node (ref "SWR4C1") (pin "2") (pinfunction "1_2") (pintype "passive"))
    )
    (net (code "67") (name "Net-(SWR4C2-1)") (class "Default")
      (node (ref "D15") (pin "A") (pinfunction "A_A") (pintype "passive"))
      (node (ref "SWR4C2") (pin "2") (pinfunction "1_2") (pintype "passive"))
    )
    (net (code "68") (name "Net-(SWR4C3-1)") (class "Default")
      (node (ref "D16") (pin "A") (pinfunction "A_A") (pintype "passive"))
      (node (ref "SWR4C3") (pin "2") (pinfunction "1_2") (pintype "passive"))
    )
    (net (code "69") (name "Net-(SWR4C4-1)") (class "Default")
      (node (ref "D17") (pin "A") (pinfunction "A_A") (pintype "passive"))
      (node (ref "SWR4C4") (pin "2") (pinfunction "1_2") (pintype "passive"))
    )
    (net (code "70") (name "Net-(SWR5C1-1)") (class "Default")
      (node (ref "D21") (pin "A") (pinfunction "A_A") (pintype "passive"))
      (node (ref "SWR5C1") (pin "2") (pinfunction "1_2") (pintype "passive"))
    )
    (net (code "71") (name "Net-(SWR5C2-1)") (class "Default")
      (node (ref "D20") (pin "A") (pinfunction "A_A") (pintype "passive"))
      (node (ref "SWR5C2") (pin "2") (pinfunction "1_2") (pintype "passive"))
    )
    (net (code "72") (name "Net-(SWR5C3-1)") (class "Default")
      (node (ref "D19") (pin "A") (pinfunction "A_A") (pintype "passive"))
      (node (ref "SWR5C3") (pin "2") (pinfunction "1_2") (pintype "passive"))
    )
    (net (code "73") (name "Net-(SWR5C4-1)") (class "Default")
      (node (ref "D18") (pin "A") (pinfunction "A_A") (pintype "passive"))
      (node (ref "SWR5C4") (pin "2") (pinfunction "1_2") (pintype "passive"))
    )
    (net (code "74") (name "Net-(U$2-IREF)") (class "Default")
      (node (ref "R6") (pin "2") (pinfunction "2_2") (pintype "passive"))
      (node (ref "U$2") (pin "5") (pinfunction "IREF_5") (pintype "bidirectional"))
    )
    (net (code "75") (name "Net-(U$2-VCOMH)") (class "Default")
      (node (ref "C34") (pin "2") (pinfunction "2_2") (pintype "passive"))
      (node (ref "U$2") (pin "3") (pinfunction "VCOMH_3") (pintype "bidirectional"))
    )
    (net (code "76") (name "Net-(U1-CC1)") (class "Default")
      (node (ref "R4") (pin "2") (pinfunction "2_2") (pintype "passive"))
      (node (ref "U1") (pin "A5") (pinfunction "CC1_A5") (pintype "bidirectional"))
    )
    (net (code "77") (name "Net-(U1-CC2)") (class "Default")
      (node (ref "R18") (pin "2") (pinfunction "2_2") (pintype "passive"))
      (node (ref "U1") (pin "B5") (pinfunction "CC2_B5") (pintype "bidirectional"))
    )
    (net (code "78") (name "Net-(U2-CC1)") (class "Default")
      (node (ref "R9") (pin "1") (pinfunction "1_1") (pintype "passive"))
      (node (ref "U2") (pin "A5") (pinfunction "CC1_A5") (pintype "bidirectional"))
    )
    (net (code "79") (name "Net-(U2-CC2)") (class "Default")
      (node (ref "R1") (pin "1") (pinfunction "1_1") (pintype "passive"))
      (node (ref "U2") (pin "B5") (pinfunction "CC2_B5") (pintype "bidirectional"))
    )
    (net (code "80") (name "Net-(U3-GPIO1)") (class "Default")
      (node (ref "C1") (pin "2") (pinfunction "2_2") (pintype "passive"))
      (node (ref "R8") (pin "1") (pinfunction "1_1") (pintype "passive"))
      (node (ref "U3") (pin "6") (pinfunction "GPIO1_6") (pintype "bidirectional"))
    )
    (net (code "81") (name "Net-(U3-GPIO2)") (class "Default")
      (node (ref "C2") (pin "2") (pinfunction "2_2") (pintype "passive"))
      (node (ref "R13") (pin "1") (pinfunction "1_1") (pintype "passive"))
      (node (ref "U3") (pin "7") (pinfunction "GPIO2_7") (pintype "bidirectional"))
    )
    (net (code "82") (name "Net-(U3-GPIO4)") (class "Default")
      (node (ref "C9") (pin "2") (pinfunction "2_2") (pintype "passive"))
      (node (ref "R14") (pin "1") (pinfunction "1_1") (pintype "passive"))
      (node (ref "U3") (pin "9") (pinfunction "GPIO4_9") (pintype "bidirectional"))
    )
    (net (code "83") (name "Net-(U3-GPIO5)") (class "Default")
      (node (ref "C10") (pin "2") (pinfunction "2_2") (pintype "passive"))
      (node (ref "R15") (pin "1") (pinfunction "1_1") (pintype "passive"))
      (node (ref "U3") (pin "10") (pinfunction "GPIO5_10") (pintype "bidirectional"))
    )
    (net (code "84") (name "Net-(U3-GPIO33)") (class "Default")
      (node (ref "SH1") (pin "7") (pinfunction "7_7") (pintype "passive"))
      (node (ref "U3") (pin "38") (pinfunction "GPIO33_38") (pintype "bidirectional"))
    )
    (net (code "85") (name "Net-(U3-LNA_IN)") (class "Default")
      (node (ref "U3") (pin "1") (pinfunction "LNA_IN_1") (pintype "bidirectional"))
      (node (ref "X1") (pin "3") (pinfunction "SIGNAL_3") (pintype "passive"))
    )
    (net (code "86") (name "Net-(U3-SPICLK_N)") (class "Default")
      (node (ref "SH1") (pin "5") (pinfunction "5_5") (pintype "passive"))
      (node (ref "U3") (pin "36") (pinfunction "SPICLK_N_36") (pintype "bidirectional"))
    )
    (net (code "87") (name "Net-(U3-SPICLK_P)") (class "Default")
      (node (ref "SH1") (pin "6") (pinfunction "6_6") (pintype "passive"))
      (node (ref "U3") (pin "37") (pinfunction "SPICLK_P_37") (pintype "bidirectional"))
    )
    (net (code "88") (name "Net-(U3-U0RXD)") (class "Default")
      (node (ref "SH1") (pin "9") (pinfunction "9_9") (pintype "passive"))
      (node (ref "U3") (pin "50") (pinfunction "U0RXD_50") (pintype "bidirectional"))
    )
    (net (code "89") (name "Net-(U3-U0TXD)") (class "Default")
      (node (ref "SH1") (pin "10") (pinfunction "10_10") (pintype "passive"))
      (node (ref "U3") (pin "49") (pinfunction "U0TXD_49") (pintype "bidirectional"))
    )
    (net (code "90") (name "Net-(U3-XTAL_N)") (class "Default")
      (node (ref "C3") (pin "1") (pinfunction "1_1") (pintype "passive"))
      (node (ref "U3") (pin "53") (pinfunction "XTAL_N_53") (pintype "output"))
      (node (ref "Y1") (pin "3") (pinfunction "2_3") (pintype "passive"))
    )
    (net (code "91") (name "Net-(U3-XTAL_P)") (class "Default")
      (node (ref "C8") (pin "1") (pinfunction "1_1") (pintype "passive"))
      (node (ref "U3") (pin "54") (pinfunction "XTAL_P_54") (pintype "input"))
      (node (ref "Y1") (pin "1") (pinfunction "1_1") (pintype "passive"))
    )
    (net (code "92") (name "Net-(U19-FB)") (class "Default")
      (node (ref "C35") (pin "1") (pinfunction "1_1") (pintype "passive"))
      (node (ref "R10") (pin "1") (pinfunction "1_1") (pintype "passive"))
      (node (ref "R7") (pin "2") (pinfunction "2_2") (pintype "passive"))
      (node (ref "U19") (pin "3") (pinfunction "FB_3") (pintype "bidirectional"))
    )
    (net (code "93") (name "Net-(U19-SW)") (class "Default")
      (node (ref "D1") (pin "A") (pinfunction "A_A") (pintype "passive"))
      (node (ref "L2") (pin "2") (pinfunction "2_2") (pintype "passive"))
      (node (ref "U19") (pin "1") (pinfunction "SW_1") (pintype "bidirectional"))
    )
    (net (code "94") (name "Net-(X2-SIGNAL)") (class "Default")
      (node (ref "R3") (pin "1") (pinfunction "1_1") (pintype "passive"))
      (node (ref "X2") (pin "3") (pinfunction "SIGNAL_3") (pintype "passive"))
    )
    (net (code "95") (name "OLED_CS") (class "Default")
      (node (ref "R12") (pin "1") (pinfunction "1_1") (pintype "passive"))
      (node (ref "U$2") (pin "6") (pinfunction "CS_6") (pintype "bidirectional"))
      (node (ref "U3") (pin "19") (pinfunction "GPIO14_19") (pintype "bidirectional"))
    )
    (net (code "96") (name "OLED_RESET") (class "Default")
      (node (ref "R17") (pin "2") (pinfunction "2_2") (pintype "passive"))
      (node (ref "U$2") (pin "7") (pinfunction "RES_7") (pintype "bidirectional"))
      (node (ref "U3") (pin "18") (pinfunction "GPIO13_18") (pintype "bidirectional"))
    )
    (net (code "97") (name "ROW0") (class "Default")
      (node (ref "D2") (pin "C") (pinfunction "C_C") (pintype "passive"))
      (node (ref "D3") (pin "C") (pinfunction "C_C") (pintype "passive"))
      (node (ref "D4") (pin "C") (pinfunction "C_C") (pintype "passive"))
      (node (ref "D5") (pin "C") (pinfunction "C_C") (pintype "passive"))
      (node (ref "U3") (pin "51") (pinfunction "GPIO45_51") (pintype "bidirectional"))
    )
    (net (code "98") (name "ROW1") (class "Default")
      (node (ref "D6") (pin "C") (pinfunction "C_C") (pintype "passive"))
      (node (ref "D7") (pin "C") (pinfunction "C_C") (pintype "passive"))
      (node (ref "D8") (pin "C") (pinfunction "C_C") (pintype "passive"))
      (node (ref "D9") (pin "C") (pinfunction "C_C") (pintype "passive"))
      (node (ref "U3") (pin "45") (pinfunction "MTDO_45") (pintype "bidirectional"))
    )
    (net (code "99") (name "ROW2") (class "Default")
      (node (ref "D10") (pin "C") (pinfunction "C_C") (pintype "passive"))
      (node (ref "D11") (pin "C") (pinfunction "C_C") (pintype "passive"))
      (node (ref "D12") (pin "C") (pinfunction "C_C") (pintype "passive"))
      (node (ref "D13") (pin "C") (pinfunction "C_C") (pintype "passive"))
      (node (ref "U3") (pin "42") (pinfunction "GPIO37_42") (pintype "bidirectional"))
    )
    (net (code "100") (name "ROW3") (class "Default")
      (node (ref "D14") (pin "C") (pinfunction "C_C") (pintype "passive"))
      (node (ref "D15") (pin "C") (pinfunction "C_C") (pintype "passive"))
      (node (ref "D16") (pin "C") (pinfunction "C_C") (pintype "passive"))
      (node (ref "D17") (pin "C") (pinfunction "C_C") (pintype "passive"))
      (node (ref "U3") (pin "41") (pinfunction "GPIO36_41") (pintype "bidirectional"))
    )
    (net (code "101") (name "ROW4") (class "Default")
      (node (ref "D18") (pin "C") (pinfunction "C_C") (pintype "passive"))
      (node (ref "D19") (pin "C") (pinfunction "C_C") (pintype "passive"))
      (node (ref "D20") (pin "C") (pinfunction "C_C") (pintype "passive"))
      (node (ref "D21") (pin "C") (pinfunction "C_C") (pintype "passive"))
      (node (ref "U3") (pin "40") (pinfunction "GPIO35_40") (pintype "bidirectional"))
    )
    (net (code "102") (name "SCLK") (class "Default")
      (node (ref "U$2") (pin "9") (pinfunction "D0_9") (pintype "bidirectional"))
      (node (ref "U3") (pin "16") (pinfunction "GPIO11_16") (pintype "bidirectional"))
    )
    (net (code "103") (name "unconnected-(JP2-Pad3)") (class "Default")
      (node (ref "JP2") (pin "3") (pinfunction "3_3") (pintype "passive"))
    )
    (net (code "104") (name "unconnected-(LED_R5C1-DO-PadDOUT)") (class "Default")
      (node (ref "LED_R5C1") (pin "DOUT") (pinfunction "DO_DOUT") (pintype "output"))
    )
    (net (code "105") (name "unconnected-(R3-Pad2)") (class "Default")
      (node (ref "R3") (pin "2") (pinfunction "2_2") (pintype "passive"))
    )
    (net (code "106") (name "unconnected-(SD1-DAT1-Pad8)") (class "Default")
      (node (ref "SD1") (pin "8") (pinfunction "DAT1_8") (pintype "bidirectional"))
    )
    (net (code "107") (name "unconnected-(SD1-DAT2-Pad1)") (class "Default")
      (node (ref "SD1") (pin "1") (pinfunction "DAT2_1") (pintype "bidirectional"))
    )
    (net (code "108") (name "unconnected-(U1-SBU1-PadA8)") (class "Default")
      (node (ref "U1") (pin "A8") (pinfunction "SBU1_A8") (pintype "bidirectional"))
    )
    (net (code "109") (name "unconnected-(U1-SBU2-PadB8)") (class "Default")
      (node (ref "U1") (pin "B8") (pinfunction "SBU2_B8") (pintype "bidirectional"))
    )
    (net (code "110") (name "unconnected-(U2-SBU1-PadA8)") (class "Default")
      (node (ref "U2") (pin "A8") (pinfunction "SBU1_A8") (pintype "bidirectional"))
    )
    (net (code "111") (name "unconnected-(U2-SBU2-PadB8)") (class "Default")
      (node (ref "U2") (pin "B8") (pinfunction "SBU2_B8") (pintype "bidirectional"))
    )
    (net (code "112") (name "unconnected-(U3-SPICLK-Pad33)") (class "Default")
      (node (ref "U3") (pin "33") (pinfunction "SPICLK_33") (pintype "bidirectional"))
    )
    (net (code "113") (name "unconnected-(U3-SPICS0-Pad32)") (class "Default")
      (node (ref "U3") (pin "32") (pinfunction "SPICS0_32") (pintype "bidirectional"))
    )
    (net (code "114") (name "unconnected-(U3-SPICS1-Pad28)") (class "Default")
      (node (ref "U3") (pin "28") (pinfunction "SPICS1_28") (pintype "bidirectional"))
    )
    (net (code "115") (name "unconnected-(U3-SPID-Pad35)") (class "Default")
      (node (ref "U3") (pin "35") (pinfunction "SPID_35") (pintype "bidirectional"))
    )
    (net (code "116") (name "unconnected-(U3-SPIHD-Pad30)") (class "Default")
      (node (ref "U3") (pin "30") (pinfunction "SPIHD_30") (pintype "bidirectional"))
    )
    (net (code "117") (name "unconnected-(U3-SPIQ-Pad34)") (class "Default")
      (node (ref "U3") (pin "34") (pinfunction "SPIQ_34") (pintype "bidirectional"))
    )
    (net (code "118") (name "unconnected-(U3-SPIWP-Pad31)") (class "Default")
      (node (ref "U3") (pin "31") (pinfunction "SPIWP_31") (pintype "bidirectional"))
    )
  )
)
